# Komar.net
KiCad netlist of a schematic drawn in EAGLE
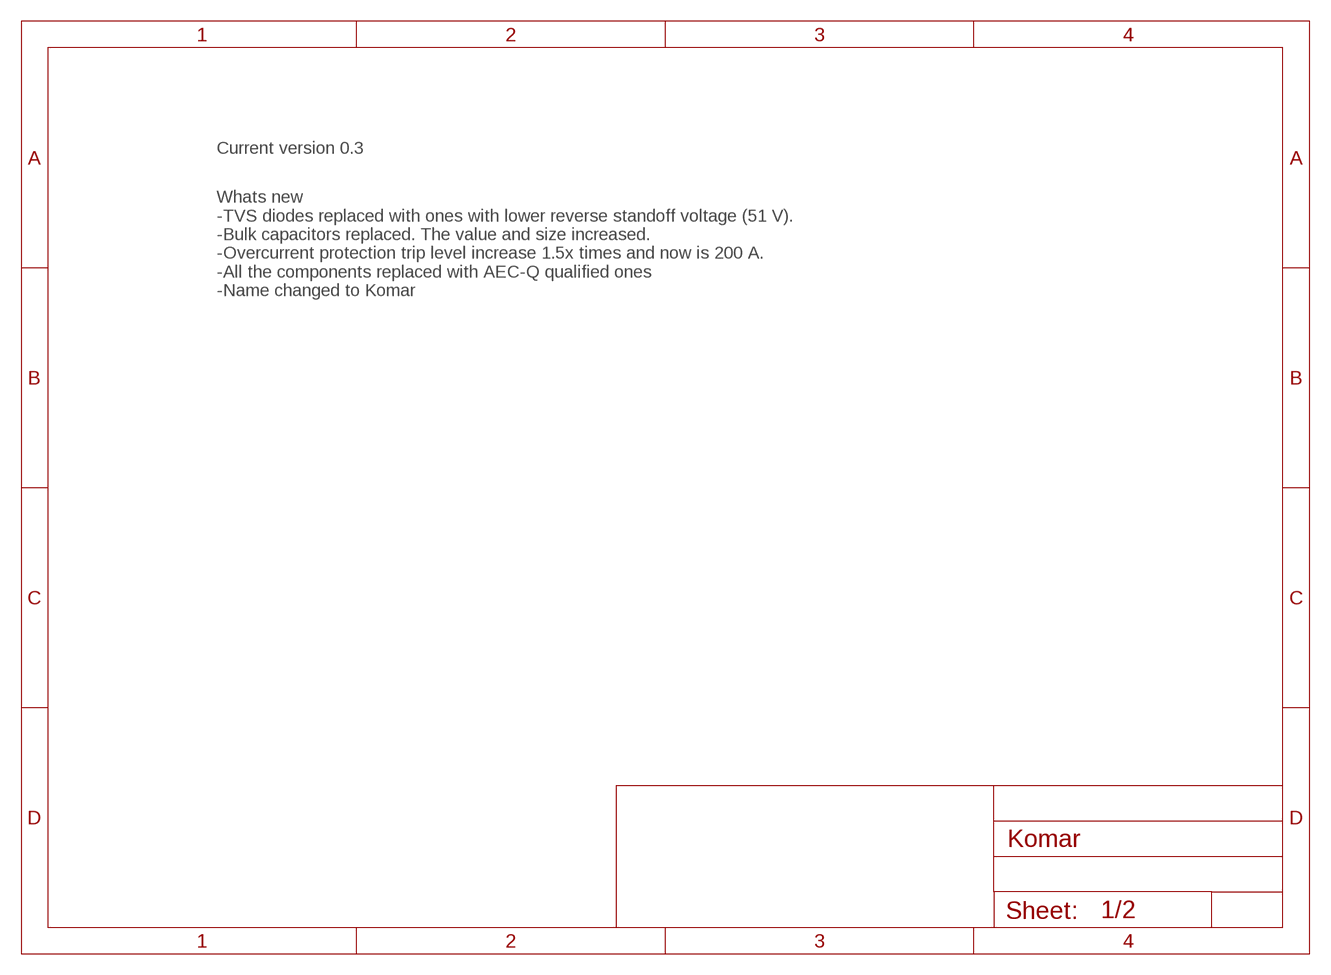
[diagram p0: schematic, sheet 1]
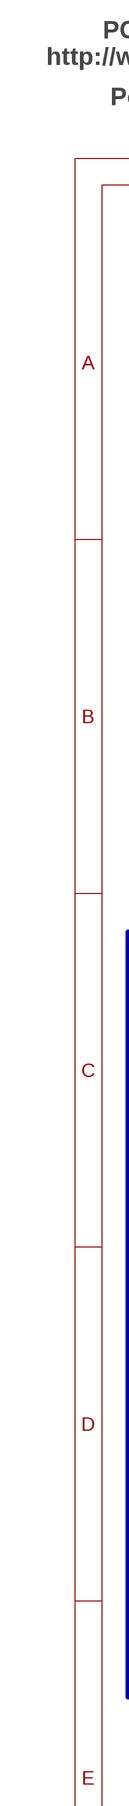
[diagram p1: schematic, sheet 2, part 1 of 2]
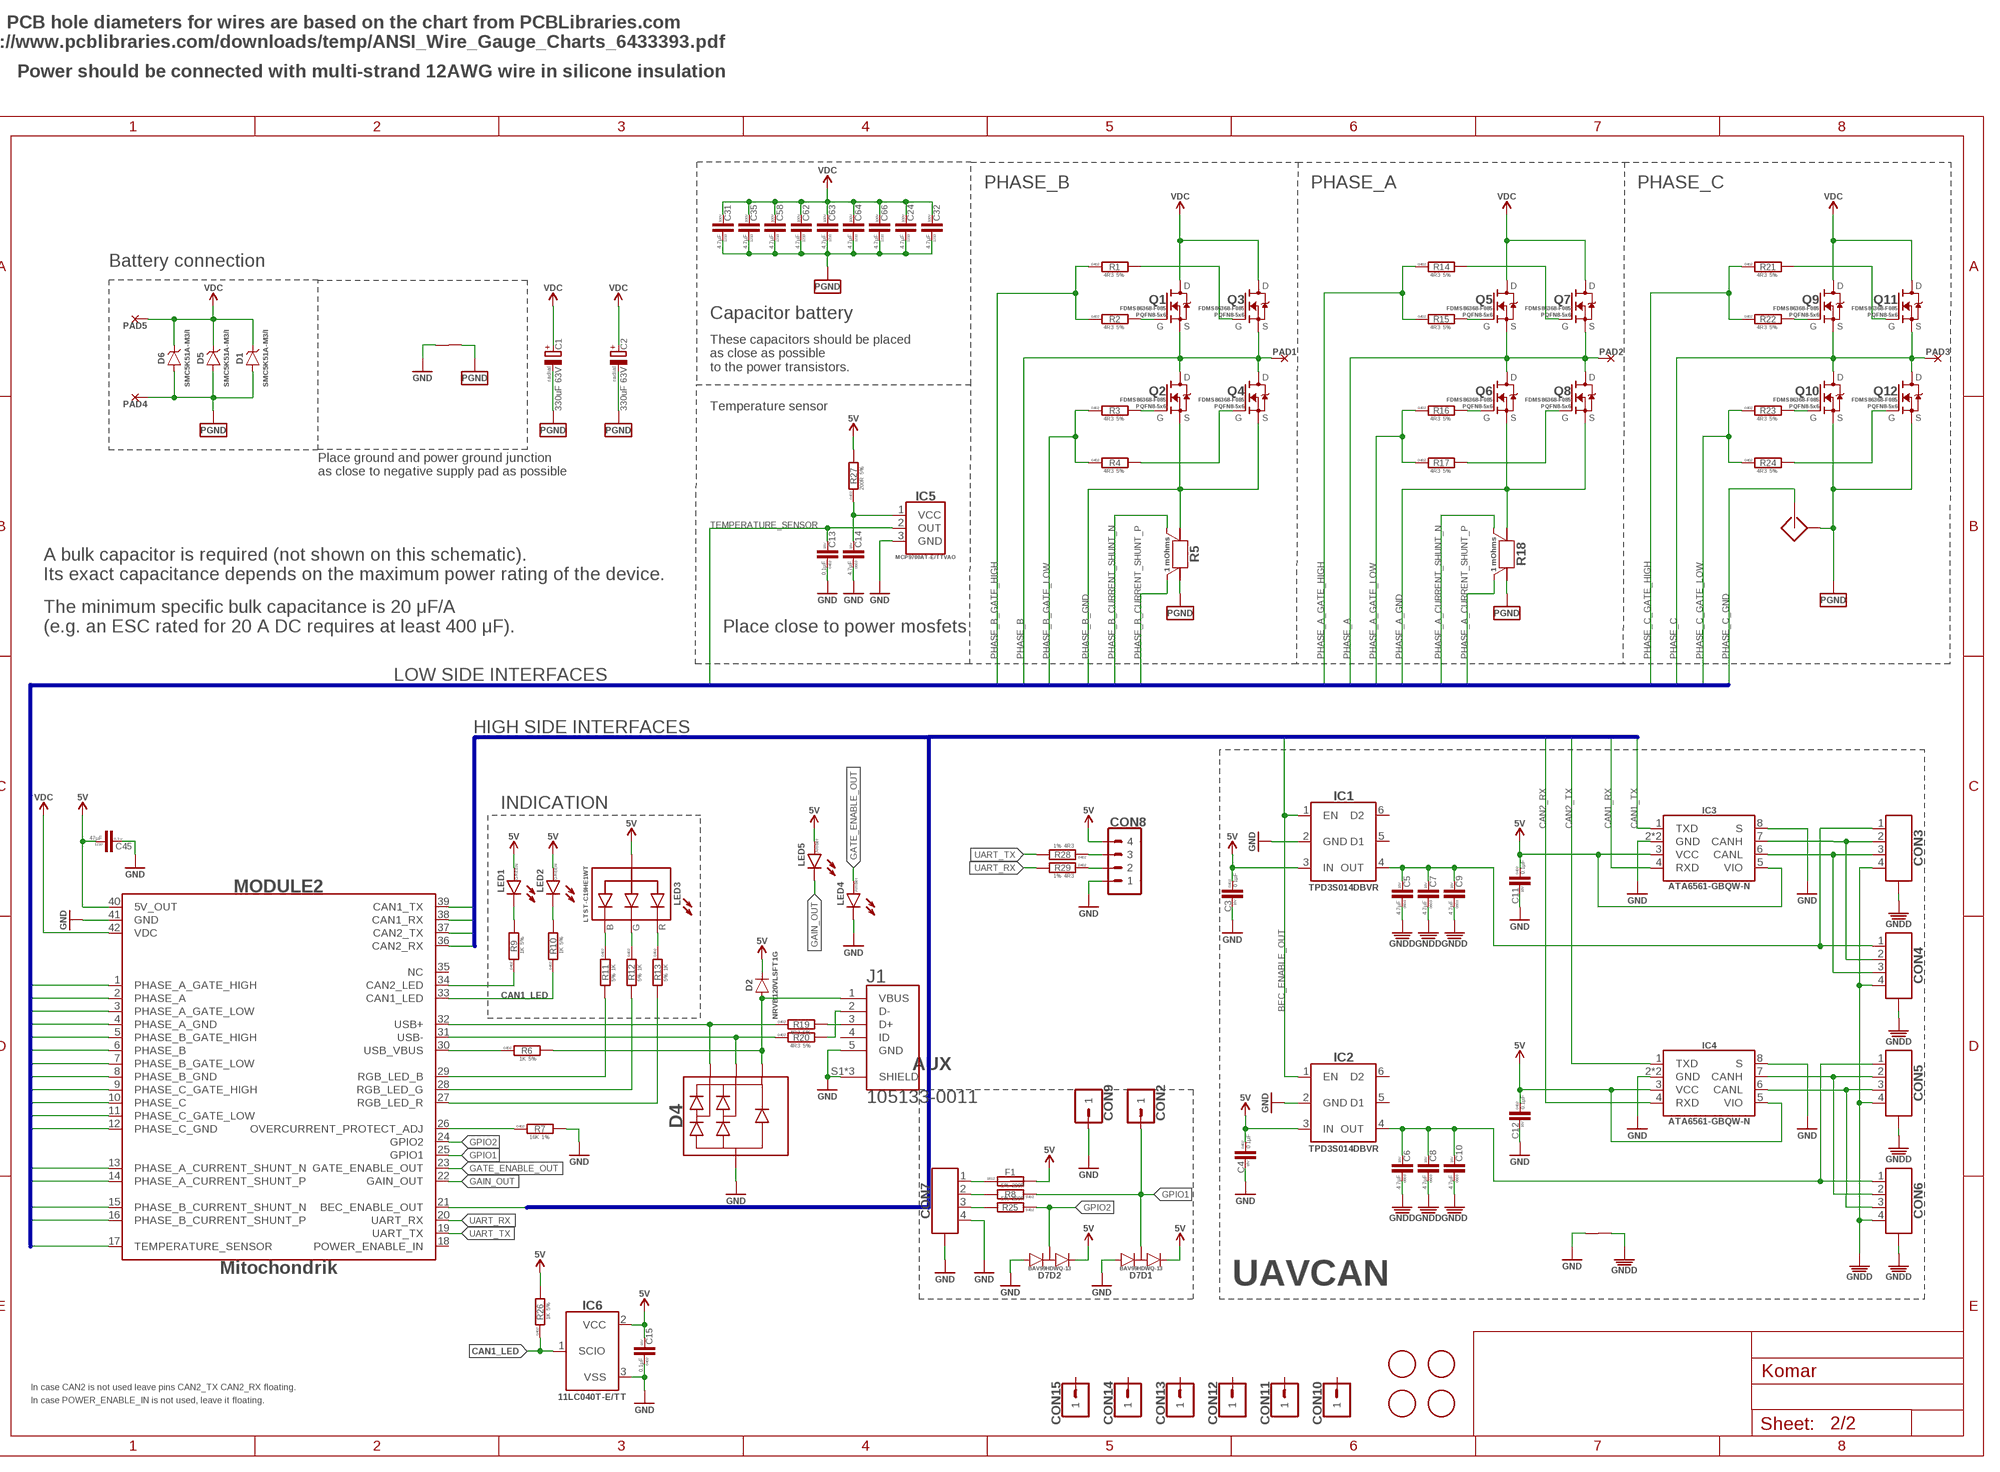
[diagram p2: schematic, sheet 2, part 2 of 2]

(export (version "E")
  (design (tool "Eeschema 10.0.6"))
  (components
    (comp (ref "C1")
      (value "330uF 63V")
      (footprint "eagle-import:SIDE_10X22")
      (fields
        (field (name "PACKAGE") "radial")
        (field (name "MANF") "EPCOS (TDK)")
        (field (name "DIGIKEY#") "565-2043-ND")
        (field (name "MANF_1") "United Chemi-Con")
        (field (name "MANF#") "ELXZ630ELL331MK20S")
      )
      (libsource (lib "eagle-import") (part "CPOL-SIDE"))
    )
    (comp (ref "C2")
      (value "330uF 63V")
      (footprint "eagle-import:SIDE_10X22")
      (fields
        (field (name "PACKAGE") "radial")
        (field (name "MANF") "EPCOS (TDK)")
        (field (name "DIGIKEY#") "565-2043-ND")
        (field (name "MANF_1") "United Chemi-Con")
        (field (name "MANF#") "ELXZ630ELL331MK20S")
      )
      (libsource (lib "eagle-import") (part "CPOL-SIDE"))
    )
    (comp (ref "C3")
      (value "0.1µF")
      (footprint "eagle-import:C0402")
      (fields
        (field (name "PACKAGE") "0402")
        (field (name "AEC-Q") "AEC-Q200")
        (field (name "DIGIKEY#") "490-7998-1-ND")
        (field (name "MANF") "Murata Electronics")
        (field (name "MANF#") "GCM155R71C104KA55J")
        (field (name "VOLTAGE") "16V")
      )
      (libsource (lib "eagle-import") (part "C-0402"))
    )
    (comp (ref "C4")
      (value "0.1µF")
      (footprint "eagle-import:C0402")
      (fields
        (field (name "PACKAGE") "0402")
        (field (name "AEC-Q") "AEC-Q200")
        (field (name "DIGIKEY#") "490-7998-1-ND")
        (field (name "MANF") "Murata Electronics")
        (field (name "MANF#") "GCM155R71C104KA55J")
        (field (name "VOLTAGE") "16V")
      )
      (libsource (lib "eagle-import") (part "C-0402"))
    )
    (comp (ref "C5")
      (value "4.7µF")
      (footprint "eagle-import:C0603")
      (fields
        (field (name "PACKAGE") "0603")
        (field (name "AEC-Q") "AEC-Q200")
        (field (name "DIGIKEY#") "490-12289-1-ND")
        (field (name "MANF") "Murata Electronics")
        (field (name "MANF#") "GRT188C81C475KE13D")
        (field (name "VOLTAGE") "16V")
      )
      (libsource (lib "eagle-import") (part "C-0603"))
    )
    (comp (ref "C6")
      (value "4.7µF")
      (footprint "eagle-import:C0603")
      (fields
        (field (name "PACKAGE") "0603")
        (field (name "AEC-Q") "AEC-Q200")
        (field (name "DIGIKEY#") "490-12289-1-ND")
        (field (name "MANF") "Murata Electronics")
        (field (name "MANF#") "GRT188C81C475KE13D")
        (field (name "VOLTAGE") "16V")
      )
      (libsource (lib "eagle-import") (part "C-0603"))
    )
    (comp (ref "C7")
      (value "4.7µF")
      (footprint "eagle-import:C0603")
      (fields
        (field (name "PACKAGE") "0603")
        (field (name "AEC-Q") "AEC-Q200")
        (field (name "DIGIKEY#") "490-12289-1-ND")
        (field (name "MANF") "Murata Electronics")
        (field (name "MANF#") "GRT188C81C475KE13D")
        (field (name "VOLTAGE") "16V")
      )
      (libsource (lib "eagle-import") (part "C-0603"))
    )
    (comp (ref "C8")
      (value "4.7µF")
      (footprint "eagle-import:C0603")
      (fields
        (field (name "PACKAGE") "0603")
        (field (name "AEC-Q") "AEC-Q200")
        (field (name "DIGIKEY#") "490-12289-1-ND")
        (field (name "MANF") "Murata Electronics")
        (field (name "MANF#") "GRT188C81C475KE13D")
        (field (name "VOLTAGE") "16V")
      )
      (libsource (lib "eagle-import") (part "C-0603"))
    )
    (comp (ref "C9")
      (value "4.7µF")
      (footprint "eagle-import:C0603")
      (fields
        (field (name "PACKAGE") "0603")
        (field (name "AEC-Q") "AEC-Q200")
        (field (name "DIGIKEY#") "490-12289-1-ND")
        (field (name "MANF") "Murata Electronics")
        (field (name "MANF#") "GRT188C81C475KE13D")
        (field (name "VOLTAGE") "16V")
      )
      (libsource (lib "eagle-import") (part "C-0603"))
    )
    (comp (ref "C10")
      (value "4.7µF")
      (footprint "eagle-import:C0603")
      (fields
        (field (name "PACKAGE") "0603")
        (field (name "AEC-Q") "AEC-Q200")
        (field (name "DIGIKEY#") "490-12289-1-ND")
        (field (name "MANF") "Murata Electronics")
        (field (name "MANF#") "GRT188C81C475KE13D")
        (field (name "VOLTAGE") "16V")
      )
      (libsource (lib "eagle-import") (part "C-0603"))
    )
    (comp (ref "C11")
      (value "0.1µF")
      (footprint "eagle-import:C0402")
      (fields
        (field (name "PACKAGE") "0402")
        (field (name "AEC-Q") "AEC-Q200")
        (field (name "DIGIKEY#") "490-7998-1-ND")
        (field (name "MANF") "Murata Electronics")
        (field (name "MANF#") "GCM155R71C104KA55J")
        (field (name "VOLTAGE") "16V")
      )
      (libsource (lib "eagle-import") (part "C-0402"))
    )
    (comp (ref "C12")
      (value "0.1µF")
      (footprint "eagle-import:C0402")
      (fields
        (field (name "PACKAGE") "0402")
        (field (name "AEC-Q") "AEC-Q200")
        (field (name "DIGIKEY#") "490-7998-1-ND")
        (field (name "MANF") "Murata Electronics")
        (field (name "MANF#") "GCM155R71C104KA55J")
        (field (name "VOLTAGE") "16V")
      )
      (libsource (lib "eagle-import") (part "C-0402"))
    )
    (comp (ref "C13")
      (value "0.1µF")
      (footprint "eagle-import:C0402")
      (fields
        (field (name "PACKAGE") "0402")
        (field (name "AEC-Q") "AEC-Q200")
        (field (name "DIGIKEY#") "490-7998-1-ND")
        (field (name "MANF") "Murata Electronics")
        (field (name "MANF#") "GCM155R71C104KA55J")
        (field (name "VOLTAGE") "16V")
      )
      (libsource (lib "eagle-import") (part "C-0402"))
    )
    (comp (ref "C14")
      (value "4.7µF")
      (footprint "eagle-import:C0603")
      (fields
        (field (name "PACKAGE") "0603")
        (field (name "AEC-Q") "AEC-Q200")
        (field (name "DIGIKEY#") "490-12289-1-ND")
        (field (name "MANF") "Murata Electronics")
        (field (name "MANF#") "GRT188C81C475KE13D")
        (field (name "VOLTAGE") "16V")
      )
      (libsource (lib "eagle-import") (part "C-0603"))
    )
    (comp (ref "C15")
      (value "0.1µF")
      (footprint "eagle-import:C0402")
      (fields
        (field (name "PACKAGE") "0402")
        (field (name "AEC-Q") "AEC-Q200")
        (field (name "DIGIKEY#") "490-7998-1-ND")
        (field (name "MANF") "Murata Electronics")
        (field (name "MANF#") "GCM155R71C104KA55J")
        (field (name "VOLTAGE") "16V")
      )
      (libsource (lib "eagle-import") (part "C-0402"))
    )
    (comp (ref "C24")
      (value "4.7µF")
      (footprint "eagle-import:C1210")
      (fields
        (field (name "PACKAGE") "1210")
        (field (name "DIGIKEY#") "490-14484-1-ND")
        (field (name "MANF") "Murata Electronics")
        (field (name "MANF#") "GCM32DC72A475KE02L")
        (field (name "OPERATING_TEMP") "-55°C ~ 125°C")
        (field (name "VOLTAGE") "100V")
      )
      (libsource (lib "eagle-import") (part "C-1210"))
    )
    (comp (ref "C31")
      (value "4.7µF")
      (footprint "eagle-import:C1210")
      (fields
        (field (name "PACKAGE") "1210")
        (field (name "DIGIKEY#") "490-14484-1-ND")
        (field (name "MANF") "Murata Electronics")
        (field (name "MANF#") "GCM32DC72A475KE02L")
        (field (name "OPERATING_TEMP") "-55°C ~ 125°C")
        (field (name "VOLTAGE") "100V")
      )
      (libsource (lib "eagle-import") (part "C-1210"))
    )
    (comp (ref "C32")
      (value "4.7µF")
      (footprint "eagle-import:C1210")
      (fields
        (field (name "PACKAGE") "1210")
        (field (name "DIGIKEY#") "490-14484-1-ND")
        (field (name "MANF") "Murata Electronics")
        (field (name "MANF#") "GCM32DC72A475KE02L")
        (field (name "OPERATING_TEMP") "-55°C ~ 125°C")
        (field (name "VOLTAGE") "100V")
      )
      (libsource (lib "eagle-import") (part "C-1210"))
    )
    (comp (ref "C35")
      (value "4.7µF")
      (footprint "eagle-import:C1210")
      (fields
        (field (name "PACKAGE") "1210")
        (field (name "DIGIKEY#") "490-14484-1-ND")
        (field (name "MANF") "Murata Electronics")
        (field (name "MANF#") "GCM32DC72A475KE02L")
        (field (name "OPERATING_TEMP") "-55°C ~ 125°C")
        (field (name "VOLTAGE") "100V")
      )
      (libsource (lib "eagle-import") (part "C-1210"))
    )
    (comp (ref "C45")
      (value "47µF")
      (footprint "eagle-import:C1210")
      (fields
        (field (name "PACKAGE") "1210")
        (field (name "DIGIKEY#") "490-4844-1-ND")
        (field (name "MANF") "Murata Electronics")
        (field (name "MANF#") "GCM32ER70J476KE19L")
        (field (name "OPERATING_TEMP") "-55°C ~ 125°C")
        (field (name "VOLTAGE") "6.3 V")
      )
      (libsource (lib "eagle-import") (part "C-1210"))
    )
    (comp (ref "C58")
      (value "4.7µF")
      (footprint "eagle-import:C1210")
      (fields
        (field (name "PACKAGE") "1210")
        (field (name "DIGIKEY#") "490-14484-1-ND")
        (field (name "MANF") "Murata Electronics")
        (field (name "MANF#") "GCM32DC72A475KE02L")
        (field (name "OPERATING_TEMP") "-55°C ~ 125°C")
        (field (name "VOLTAGE") "100V")
      )
      (libsource (lib "eagle-import") (part "C-1210"))
    )
    (comp (ref "C62")
      (value "4.7µF")
      (footprint "eagle-import:C1210")
      (fields
        (field (name "PACKAGE") "1210")
        (field (name "DIGIKEY#") "490-14484-1-ND")
        (field (name "MANF") "Murata Electronics")
        (field (name "MANF#") "GCM32DC72A475KE02L")
        (field (name "OPERATING_TEMP") "-55°C ~ 125°C")
        (field (name "VOLTAGE") "100V")
      )
      (libsource (lib "eagle-import") (part "C-1210"))
    )
    (comp (ref "C63")
      (value "4.7µF")
      (footprint "eagle-import:C1210")
      (fields
        (field (name "PACKAGE") "1210")
        (field (name "DIGIKEY#") "490-14484-1-ND")
        (field (name "MANF") "Murata Electronics")
        (field (name "MANF#") "GCM32DC72A475KE02L")
        (field (name "OPERATING_TEMP") "-55°C ~ 125°C")
        (field (name "VOLTAGE") "100V")
      )
      (libsource (lib "eagle-import") (part "C-1210"))
    )
    (comp (ref "C64")
      (value "4.7µF")
      (footprint "eagle-import:C1210")
      (fields
        (field (name "PACKAGE") "1210")
        (field (name "DIGIKEY#") "490-14484-1-ND")
        (field (name "MANF") "Murata Electronics")
        (field (name "MANF#") "GCM32DC72A475KE02L")
        (field (name "OPERATING_TEMP") "-55°C ~ 125°C")
        (field (name "VOLTAGE") "100V")
      )
      (libsource (lib "eagle-import") (part "C-1210"))
    )
    (comp (ref "C66")
      (value "4.7µF")
      (footprint "eagle-import:C1210")
      (fields
        (field (name "PACKAGE") "1210")
        (field (name "DIGIKEY#") "490-14484-1-ND")
        (field (name "MANF") "Murata Electronics")
        (field (name "MANF#") "GCM32DC72A475KE02L")
        (field (name "OPERATING_TEMP") "-55°C ~ 125°C")
        (field (name "VOLTAGE") "100V")
      )
      (libsource (lib "eagle-import") (part "C-1210"))
    )
    (comp (ref "CON2")
      (value "PINHEAD_1X01-2")
      (footprint "eagle-import:1X01-PTH-2")
      (libsource (lib "eagle-import") (part "PINHEAD_1X01-2"))
    )
    (comp (ref "CON3")
      (value "CON-4P-TABS-STRAIGHT")
      (footprint "eagle-import:JST_GH-4P-STRAIGHT")
      (fields (field (name "MANF") "JST Sales America Inc"))
      (libsource (lib "eagle-import") (part "CON-4P-TABS-STRAIGHT"))
    )
    (comp (ref "CON4")
      (value "CON-4P-TABS-STRAIGHT")
      (footprint "eagle-import:JST_GH-4P-STRAIGHT")
      (fields (field (name "MANF") "JST Sales America Inc"))
      (libsource (lib "eagle-import") (part "CON-4P-TABS-STRAIGHT"))
    )
    (comp (ref "CON5")
      (value "CON-4P-TABS-STRAIGHT")
      (footprint "eagle-import:JST_GH-4P-STRAIGHT")
      (fields (field (name "MANF") "JST Sales America Inc"))
      (libsource (lib "eagle-import") (part "CON-4P-TABS-STRAIGHT"))
    )
    (comp (ref "CON6")
      (value "CON-4P-TABS-STRAIGHT")
      (footprint "eagle-import:JST_GH-4P-STRAIGHT")
      (fields (field (name "MANF") "JST Sales America Inc"))
      (libsource (lib "eagle-import") (part "CON-4P-TABS-STRAIGHT"))
    )
    (comp (ref "CON7")
      (value "CON-4P-TABS-STRAIGHT")
      (footprint "eagle-import:JST_GH-4P-STRAIGHT")
      (fields (field (name "MANF") "JST Sales America Inc"))
      (libsource (lib "eagle-import") (part "CON-4P-TABS-STRAIGHT"))
    )
    (comp (ref "CON8")
      (value "PINHEAD_1X04-2")
      (footprint "eagle-import:1X04-PTH-2")
      (libsource (lib "eagle-import") (part "PINHEAD_1X04-2"))
    )
    (comp (ref "CON9")
      (value "PINHEAD_1X01-2")
      (footprint "eagle-import:1X01-PTH-2")
      (libsource (lib "eagle-import") (part "PINHEAD_1X01-2"))
    )
    (comp (ref "CON10")
      (value "PINHEAD_1X01-2")
      (footprint "eagle-import:1X01-PTH-2")
      (libsource (lib "eagle-import") (part "PINHEAD_1X01-2"))
    )
    (comp (ref "CON11")
      (value "PINHEAD_1X01-2")
      (footprint "eagle-import:1X01-PTH-2")
      (libsource (lib "eagle-import") (part "PINHEAD_1X01-2"))
    )
    (comp (ref "CON12")
      (value "PINHEAD_1X01-2")
      (footprint "eagle-import:1X01-PTH-2")
      (libsource (lib "eagle-import") (part "PINHEAD_1X01-2"))
    )
    (comp (ref "CON13")
      (value "PINHEAD_1X01-2")
      (footprint "eagle-import:1X01-PTH-2")
      (libsource (lib "eagle-import") (part "PINHEAD_1X01-2"))
    )
    (comp (ref "CON14")
      (value "PINHEAD_1X01-2")
      (footprint "eagle-import:1X01-PTH-2")
      (libsource (lib "eagle-import") (part "PINHEAD_1X01-2"))
    )
    (comp (ref "CON15")
      (value "PINHEAD_1X01-2")
      (footprint "eagle-import:1X01-PTH-2")
      (libsource (lib "eagle-import") (part "PINHEAD_1X01-2"))
    )
    (comp (ref "D1")
      (value "SMC5K51A-M3/I")
      (footprint "eagle-import:DO-214AB(SMC)")
      (fields
        (field (name "MANF#") "SMC5K51A-M3/I")
        (field (name "MANF") "Vishay Semiconductor Diodes Division")
      )
      (libsource (lib "eagle-import") (part "SMC5K51A-M3/I"))
    )
    (comp (ref "D2")
      (value "NRVB120VLSFT1G")
      (footprint "eagle-import:SOD123F")
      (fields (field (name "MANF#") "NRVB120VLSFT1G") (field (name "MANF") "ON Semiconductor"))
      (libsource (lib "eagle-import") (part "NRVB120VLSFT1G"))
    )
    (comp (ref "D4")
      (value "DRTR5V0U2SR-7")
      (footprint "eagle-import:SOT143B")
      (fields (field (name "MANF") "Diodes Incorporated"))
      (libsource (lib "eagle-import") (part "DRTR5V0U2SR-7"))
    )
    (comp (ref "D5")
      (value "SMC5K51A-M3/I")
      (footprint "eagle-import:DO-214AB(SMC)")
      (fields
        (field (name "MANF#") "SMC5K51A-M3/I")
        (field (name "MANF") "Vishay Semiconductor Diodes Division")
      )
      (libsource (lib "eagle-import") (part "SMC5K51A-M3/I"))
    )
    (comp (ref "D6")
      (value "SMC5K51A-M3/I")
      (footprint "eagle-import:DO-214AB(SMC)")
      (fields
        (field (name "MANF#") "SMC5K51A-M3/I")
        (field (name "MANF") "Vishay Semiconductor Diodes Division")
      )
      (libsource (lib "eagle-import") (part "SMC5K51A-M3/I"))
    )
    (comp (ref "D7")
      (value "BAV99HDWQ-13")
      (footprint "eagle-import:SOT363")
      (fields (field (name "MANF#") "BAV99HDWQ-13") (field (name "MANF") "Diodes Incorporated"))
      (libsource (lib "eagle-import") (part "BAV99HDWQ-13"))
    )
    (comp (ref "F1")
      (value "FUSE-1812")
      (footprint "eagle-import:F1812")
      (fields (field (name "PACKAGE") "1812") (field (name "MANF") "Bourns Inc."))
      (libsource (lib "eagle-import") (part "FUSE-1812"))
    )
    (comp (ref "IC1")
      (value "TPD3S014DBVR-SOT23-6")
      (footprint "eagle-import:SOT26")
      (fields (field (name "MANF#") "TPD3S014DBVR") (field (name "MANF") "Texas Instruments"))
      (libsource (lib "eagle-import") (part "TPD3S014DBVR-SOT23-6"))
    )
    (comp (ref "IC2")
      (value "TPD3S014DBVR-SOT23-6")
      (footprint "eagle-import:SOT26")
      (fields (field (name "MANF#") "TPD3S014DBVR") (field (name "MANF") "Texas Instruments"))
      (libsource (lib "eagle-import") (part "TPD3S014DBVR-SOT23-6"))
    )
    (comp (ref "IC3")
      (value "ATA6561-GBQW-N-HVSON8")
      (footprint "eagle-import:SOT782-1")
      (fields (field (name "MANF#") "ATA6561-GBQW-N") (field (name "MANF") "Microchip Technology"))
      (libsource (lib "eagle-import") (part "ATA6561-GBQW-N-HVSON8"))
    )
    (comp (ref "IC4")
      (value "ATA6561-GBQW-N-HVSON8")
      (footprint "eagle-import:SOT782-1")
      (fields (field (name "MANF#") "ATA6561-GBQW-N") (field (name "MANF") "Microchip Technology"))
      (libsource (lib "eagle-import") (part "ATA6561-GBQW-N-HVSON8"))
    )
    (comp (ref "IC5")
      (value "MCP9700AT-E/TTVAO-SOT23")
      (footprint "eagle-import:SOT23B-3")
      (fields (field (name "MANF") "Microchip Technology") (field (name "MANF#") "MCP9700AT-E/TTVAO"))
      (libsource (lib "eagle-import") (part "MCP9700-SOT23AT-E/TTVAO"))
    )
    (comp (ref "IC6")
      (value "11LC040T-E/TT")
      (footprint "eagle-import:SOT23B-3")
      (fields (field (name "MANF#") "11LC040T-E/TT") (field (name "MANF") "Microchip Technology"))
      (libsource (lib "eagle-import") (part "11LC040T-E/TT"))
    )
    (comp (ref "J1")
      (value "105133-0011")
      (footprint "eagle-import:MOLEX_105133-0011")
      (fields
        (field (name "MANF") "Molex")
        (field (name "AEC-Q") "---")
        (field (name "DIGIKEY#") "WM10134TR-ND")
        (field (name "MANF_1") "Molex")
        (field (name "MANF#") "105133-0011")
        (field (name "OPERATING_TEMP") "-35°C ~ 85°C")
      )
      (libsource (lib "eagle-import") (part "105133-0011"))
    )
    (comp (ref "LED1")
      (value "GREEN")
      (footprint "eagle-import:LED0402")
      (fields
        (field (name "COLOR") "GREEN")
        (field (name "DIGIKEY#") "1830-IN-S42BT5GCT-ND")
        (field (name "MANF") "Inolux")
        (field (name "MANF#") "IN-S42BT5G")
      )
      (libsource (lib "eagle-import") (part "LED-0402"))
    )
    (comp (ref "LED2")
      (value "GREEN")
      (footprint "eagle-import:LED0402")
      (fields
        (field (name "COLOR") "GREEN")
        (field (name "DIGIKEY#") "1830-IN-S42BT5GCT-ND")
        (field (name "MANF") "Inolux")
        (field (name "MANF#") "IN-S42BT5G")
      )
      (libsource (lib "eagle-import") (part "LED-0402"))
    )
    (comp (ref "LED3")
      (value "LTST-C19HE1WT")
      (footprint "eagle-import:0606")
      (fields (field (name "MANF#") "LTST-C19HE1WT") (field (name "MANF") "Lite-On Inc"))
      (libsource (lib "eagle-import") (part "LTST-C19HE1WT"))
    )
    (comp (ref "LED4")
      (value "ORANGE")
      (footprint "eagle-import:LED0402")
      (fields
        (field (name "COLOR") "Amber")
        (field (name "DIGIKEY#") "1830-IN-S42BT5ACT-ND")
        (field (name "MANF") "Inolux")
        (field (name "MANF#") "IN-S42BT5A")
      )
      (libsource (lib "eagle-import") (part "LED-0402"))
    )
    (comp (ref "LED5")
      (value "ORANGE")
      (footprint "eagle-import:LED0402")
      (fields
        (field (name "COLOR") "Amber")
        (field (name "DIGIKEY#") "1830-IN-S42BT5ACT-ND")
        (field (name "MANF") "Inolux")
        (field (name "MANF#") "IN-S42BT5A")
      )
      (libsource (lib "eagle-import") (part "LED-0402"))
    )
    (comp (ref "MODULE2")
      (value "MITOCHONDRIK_LV-TH")
      (footprint "eagle-import:MITOHONDRIK-TH")
      (fields (field (name "MANF#") "Mitochondrik") (field (name "MANF") "Zubax Robotics"))
      (libsource (lib "eagle-import") (part "MITOCHONDRIK_LV-TH"))
    )
    (comp (ref "PAD1")
      (value "PAD-HOLE_2.4_SQUARE")
      (footprint "eagle-import:HOLE_2.4")
      (libsource (lib "eagle-import") (part "PAD-HOLE_2.4_SQUARE"))
    )
    (comp (ref "PAD2")
      (value "PAD-HOLE_2.4_SQUARE")
      (footprint "eagle-import:HOLE_2.4")
      (libsource (lib "eagle-import") (part "PAD-HOLE_2.4_SQUARE"))
    )
    (comp (ref "PAD3")
      (value "PAD-HOLE_2.4_SQUARE")
      (footprint "eagle-import:HOLE_2.4")
      (libsource (lib "eagle-import") (part "PAD-HOLE_2.4_SQUARE"))
    )
    (comp (ref "PAD4")
      (value "PAD-HOLE_2.8_SQUARE")
      (footprint "eagle-import:HOLE_2.8")
      (libsource (lib "eagle-import") (part "PAD-HOLE_2.8_SQUARE"))
    )
    (comp (ref "PAD5")
      (value "PAD-HOLE_2.8_SQUARE")
      (footprint "eagle-import:HOLE_2.8")
      (libsource (lib "eagle-import") (part "PAD-HOLE_2.8_SQUARE"))
    )
    (comp (ref "Q1")
      (value "FDMS86368-F085")
      (footprint "eagle-import:PQFN8_5X6")
      (fields
        (field (name "MANF#") "FDMS86368-F085")
        (field (name "PACKAGE") "PQFN8-5x6")
        (field (name "MANF") "ON Semiconductor")
      )
      (libsource (lib "eagle-import") (part "FDMS86368-F085"))
    )
    (comp (ref "Q2")
      (value "FDMS86368-F085")
      (footprint "eagle-import:PQFN8_5X6")
      (fields
        (field (name "MANF#") "FDMS86368-F085")
        (field (name "PACKAGE") "PQFN8-5x6")
        (field (name "MANF") "ON Semiconductor")
      )
      (libsource (lib "eagle-import") (part "FDMS86368-F085"))
    )
    (comp (ref "Q3")
      (value "FDMS86368-F085")
      (footprint "eagle-import:PQFN8_5X6")
      (fields
        (field (name "MANF#") "FDMS86368-F085")
        (field (name "PACKAGE") "PQFN8-5x6")
        (field (name "MANF") "ON Semiconductor")
      )
      (libsource (lib "eagle-import") (part "FDMS86368-F085"))
    )
    (comp (ref "Q4")
      (value "FDMS86368-F085")
      (footprint "eagle-import:PQFN8_5X6")
      (fields
        (field (name "MANF#") "FDMS86368-F085")
        (field (name "PACKAGE") "PQFN8-5x6")
        (field (name "MANF") "ON Semiconductor")
      )
      (libsource (lib "eagle-import") (part "FDMS86368-F085"))
    )
    (comp (ref "Q5")
      (value "FDMS86368-F085")
      (footprint "eagle-import:PQFN8_5X6")
      (fields
        (field (name "MANF#") "FDMS86368-F085")
        (field (name "PACKAGE") "PQFN8-5x6")
        (field (name "MANF") "ON Semiconductor")
      )
      (libsource (lib "eagle-import") (part "FDMS86368-F085"))
    )
    (comp (ref "Q6")
      (value "FDMS86368-F085")
      (footprint "eagle-import:PQFN8_5X6")
      (fields
        (field (name "MANF#") "FDMS86368-F085")
        (field (name "PACKAGE") "PQFN8-5x6")
        (field (name "MANF") "ON Semiconductor")
      )
      (libsource (lib "eagle-import") (part "FDMS86368-F085"))
    )
    (comp (ref "Q7")
      (value "FDMS86368-F085")
      (footprint "eagle-import:PQFN8_5X6")
      (fields
        (field (name "MANF#") "FDMS86368-F085")
        (field (name "PACKAGE") "PQFN8-5x6")
        (field (name "MANF") "ON Semiconductor")
      )
      (libsource (lib "eagle-import") (part "FDMS86368-F085"))
    )
    (comp (ref "Q8")
      (value "FDMS86368-F085")
      (footprint "eagle-import:PQFN8_5X6")
      (fields
        (field (name "MANF#") "FDMS86368-F085")
        (field (name "PACKAGE") "PQFN8-5x6")
        (field (name "MANF") "ON Semiconductor")
      )
      (libsource (lib "eagle-import") (part "FDMS86368-F085"))
    )
    (comp (ref "Q9")
      (value "FDMS86368-F085")
      (footprint "eagle-import:PQFN8_5X6")
      (fields
        (field (name "MANF#") "FDMS86368-F085")
        (field (name "PACKAGE") "PQFN8-5x6")
        (field (name "MANF") "ON Semiconductor")
      )
      (libsource (lib "eagle-import") (part "FDMS86368-F085"))
    )
    (comp (ref "Q10")
      (value "FDMS86368-F085")
      (footprint "eagle-import:PQFN8_5X6")
      (fields
        (field (name "MANF#") "FDMS86368-F085")
        (field (name "PACKAGE") "PQFN8-5x6")
        (field (name "MANF") "ON Semiconductor")
      )
      (libsource (lib "eagle-import") (part "FDMS86368-F085"))
    )
    (comp (ref "Q11")
      (value "FDMS86368-F085")
      (footprint "eagle-import:PQFN8_5X6")
      (fields
        (field (name "MANF#") "FDMS86368-F085")
        (field (name "PACKAGE") "PQFN8-5x6")
        (field (name "MANF") "ON Semiconductor")
      )
      (libsource (lib "eagle-import") (part "FDMS86368-F085"))
    )
    (comp (ref "Q12")
      (value "FDMS86368-F085")
      (footprint "eagle-import:PQFN8_5X6")
      (fields
        (field (name "MANF#") "FDMS86368-F085")
        (field (name "PACKAGE") "PQFN8-5x6")
        (field (name "MANF") "ON Semiconductor")
      )
      (libsource (lib "eagle-import") (part "FDMS86368-F085"))
    )
    (comp (ref "R1")
      (value "4R3")
      (footprint "eagle-import:R0402")
      (fields
        (field (name "PACKAGE") "0402")
        (field (name "TOLERANCE") "5%")
        (field (name "AEC-Q") "AEC-Q200")
        (field (name "DIGIKEY#") "P4.3JCT-ND")
        (field (name "MANF") "Panasonic Electronic Components")
        (field (name "MANF#") "ERJ-2GEJ4R3X")
      )
      (libsource (lib "eagle-import") (part "R-0402-5%"))
    )
    (comp (ref "R2")
      (value "4R3")
      (footprint "eagle-import:R0402")
      (fields
        (field (name "PACKAGE") "0402")
        (field (name "TOLERANCE") "5%")
        (field (name "AEC-Q") "AEC-Q200")
        (field (name "DIGIKEY#") "P4.3JCT-ND")
        (field (name "MANF") "Panasonic Electronic Components")
        (field (name "MANF#") "ERJ-2GEJ4R3X")
      )
      (libsource (lib "eagle-import") (part "R-0402-5%"))
    )
    (comp (ref "R3")
      (value "4R3")
      (footprint "eagle-import:R0402")
      (fields
        (field (name "PACKAGE") "0402")
        (field (name "TOLERANCE") "5%")
        (field (name "AEC-Q") "AEC-Q200")
        (field (name "DIGIKEY#") "P4.3JCT-ND")
        (field (name "MANF") "Panasonic Electronic Components")
        (field (name "MANF#") "ERJ-2GEJ4R3X")
      )
      (libsource (lib "eagle-import") (part "R-0402-5%"))
    )
    (comp (ref "R4")
      (value "4R3")
      (footprint "eagle-import:R0402")
      (fields
        (field (name "PACKAGE") "0402")
        (field (name "TOLERANCE") "5%")
        (field (name "AEC-Q") "AEC-Q200")
        (field (name "DIGIKEY#") "P4.3JCT-ND")
        (field (name "MANF") "Panasonic Electronic Components")
        (field (name "MANF#") "ERJ-2GEJ4R3X")
      )
      (libsource (lib "eagle-import") (part "R-0402-5%"))
    )
    (comp (ref "R5")
      (value "1 mOhms")
      (footprint "eagle-import:R2512-KELVIN")
      (fields
        (field (name "MANF") "Stackpole Electronics Inc.")
        (field (name "POWER") "2W")
        (field (name "TOLERANCE") "±1%")
        (field (name "DIGIKEY#") "CRE2512-FZ-R001E-3CT-ND")
        (field (name "MANF_1") "Bourns Inc.")
        (field (name "MANF#") "CRE2512-FZ-R001E-3")
        (field (name "POWER_1") "3W")
      )
      (libsource (lib "eagle-import") (part "CURRENT_SHUNT_KELVIN-2512-KELVIN-0.001R"))
    )
    (comp (ref "R6")
      (value "1K")
      (footprint "eagle-import:R0402")
      (fields
        (field (name "PACKAGE") "0402")
        (field (name "TOLERANCE") "5%")
        (field (name "AEC-Q") "AEC-Q200")
        (field (name "DIGIKEY#") "P1.00KLCT-ND")
        (field (name "MANF") "Panasonic Electronic Components")
        (field (name "MANF#") "ERJ-2RKF1001X")
      )
      (libsource (lib "eagle-import") (part "R-0402-5%"))
    )
    (comp (ref "R7")
      (value "16K")
      (footprint "eagle-import:R0402")
      (fields
        (field (name "PACKAGE") "0402")
        (field (name "TOLERANCE") "1%")
        (field (name "AEC-Q") "AEC-Q200")
        (field (name "DIGIKEY#") "P124444CT-ND")
        (field (name "MANF") "Panasonic Electronic Components")
        (field (name "MANF#") "ERJ-PA2F1602X")
      )
      (libsource (lib "eagle-import") (part "R-0402-1%"))
    )
    (comp (ref "R8")
      (value "200R")
      (footprint "eagle-import:R0402")
      (fields
        (field (name "PACKAGE") "0402")
        (field (name "TOLERANCE") "5%")
        (field (name "AEC-Q") "AEC-Q200")
        (field (name "DIGIKEY#") "P200JCT-ND")
        (field (name "MANF") "Panasonic Electronic Components")
        (field (name "MANF#") "ERJ-2GEJ201X")
      )
      (libsource (lib "eagle-import") (part "R-0402-5%"))
    )
    (comp (ref "R9")
      (value "1K")
      (footprint "eagle-import:R0402")
      (fields
        (field (name "PACKAGE") "0402")
        (field (name "TOLERANCE") "5%")
        (field (name "AEC-Q") "AEC-Q200")
        (field (name "DIGIKEY#") "P1.00KLCT-ND")
        (field (name "MANF") "Panasonic Electronic Components")
        (field (name "MANF#") "ERJ-2RKF1001X")
      )
      (libsource (lib "eagle-import") (part "R-0402-5%"))
    )
    (comp (ref "R10")
      (value "1K")
      (footprint "eagle-import:R0402")
      (fields
        (field (name "PACKAGE") "0402")
        (field (name "TOLERANCE") "5%")
        (field (name "AEC-Q") "AEC-Q200")
        (field (name "DIGIKEY#") "P1.00KLCT-ND")
        (field (name "MANF") "Panasonic Electronic Components")
        (field (name "MANF#") "ERJ-2RKF1001X")
      )
      (libsource (lib "eagle-import") (part "R-0402-5%"))
    )
    (comp (ref "R11")
      (value "1K")
      (footprint "eagle-import:R0402")
      (fields
        (field (name "PACKAGE") "0402")
        (field (name "TOLERANCE") "5%")
        (field (name "AEC-Q") "AEC-Q200")
        (field (name "DIGIKEY#") "P1.00KLCT-ND")
        (field (name "MANF") "Panasonic Electronic Components")
        (field (name "MANF#") "ERJ-2RKF1001X")
      )
      (libsource (lib "eagle-import") (part "R-0402-5%"))
    )
    (comp (ref "R12")
      (value "1K")
      (footprint "eagle-import:R0402")
      (fields
        (field (name "PACKAGE") "0402")
        (field (name "TOLERANCE") "5%")
        (field (name "AEC-Q") "AEC-Q200")
        (field (name "DIGIKEY#") "P1.00KLCT-ND")
        (field (name "MANF") "Panasonic Electronic Components")
        (field (name "MANF#") "ERJ-2RKF1001X")
      )
      (libsource (lib "eagle-import") (part "R-0402-5%"))
    )
    (comp (ref "R13")
      (value "1K")
      (footprint "eagle-import:R0402")
      (fields
        (field (name "PACKAGE") "0402")
        (field (name "TOLERANCE") "5%")
        (field (name "AEC-Q") "AEC-Q200")
        (field (name "DIGIKEY#") "P1.00KLCT-ND")
        (field (name "MANF") "Panasonic Electronic Components")
        (field (name "MANF#") "ERJ-2RKF1001X")
      )
      (libsource (lib "eagle-import") (part "R-0402-5%"))
    )
    (comp (ref "R14")
      (value "4R3")
      (footprint "eagle-import:R0402")
      (fields
        (field (name "PACKAGE") "0402")
        (field (name "TOLERANCE") "5%")
        (field (name "AEC-Q") "AEC-Q200")
        (field (name "DIGIKEY#") "P4.3JCT-ND")
        (field (name "MANF") "Panasonic Electronic Components")
        (field (name "MANF#") "ERJ-2GEJ4R3X")
      )
      (libsource (lib "eagle-import") (part "R-0402-5%"))
    )
    (comp (ref "R15")
      (value "4R3")
      (footprint "eagle-import:R0402")
      (fields
        (field (name "PACKAGE") "0402")
        (field (name "TOLERANCE") "5%")
        (field (name "AEC-Q") "AEC-Q200")
        (field (name "DIGIKEY#") "P4.3JCT-ND")
        (field (name "MANF") "Panasonic Electronic Components")
        (field (name "MANF#") "ERJ-2GEJ4R3X")
      )
      (libsource (lib "eagle-import") (part "R-0402-5%"))
    )
    (comp (ref "R16")
      (value "4R3")
      (footprint "eagle-import:R0402")
      (fields
        (field (name "PACKAGE") "0402")
        (field (name "TOLERANCE") "5%")
        (field (name "AEC-Q") "AEC-Q200")
        (field (name "DIGIKEY#") "P4.3JCT-ND")
        (field (name "MANF") "Panasonic Electronic Components")
        (field (name "MANF#") "ERJ-2GEJ4R3X")
      )
      (libsource (lib "eagle-import") (part "R-0402-5%"))
    )
    (comp (ref "R17")
      (value "4R3")
      (footprint "eagle-import:R0402")
      (fields
        (field (name "PACKAGE") "0402")
        (field (name "TOLERANCE") "5%")
        (field (name "AEC-Q") "AEC-Q200")
        (field (name "DIGIKEY#") "P4.3JCT-ND")
        (field (name "MANF") "Panasonic Electronic Components")
        (field (name "MANF#") "ERJ-2GEJ4R3X")
      )
      (libsource (lib "eagle-import") (part "R-0402-5%"))
    )
    (comp (ref "R18")
      (value "1 mOhms")
      (footprint "eagle-import:R2512-KELVIN")
      (fields
        (field (name "MANF") "Stackpole Electronics Inc.")
        (field (name "POWER") "2W")
        (field (name "TOLERANCE") "±1%")
        (field (name "DIGIKEY#") "CRE2512-FZ-R001E-3CT-ND")
        (field (name "MANF_1") "Bourns Inc.")
        (field (name "MANF#") "CRE2512-FZ-R001E-3")
        (field (name "POWER_1") "3W")
      )
      (libsource (lib "eagle-import") (part "CURRENT_SHUNT_KELVIN-2512-KELVIN-0.001R"))
    )
    (comp (ref "R19")
      (value "4R3")
      (footprint "eagle-import:R0402")
      (fields
        (field (name "PACKAGE") "0402")
        (field (name "TOLERANCE") "5%")
        (field (name "AEC-Q") "AEC-Q200")
        (field (name "DIGIKEY#") "P4.3JCT-ND")
        (field (name "MANF") "Panasonic Electronic Components")
        (field (name "MANF#") "ERJ-2GEJ4R3X")
      )
      (libsource (lib "eagle-import") (part "R-0402-5%"))
    )
    (comp (ref "R20")
      (value "4R3")
      (footprint "eagle-import:R0402")
      (fields
        (field (name "PACKAGE") "0402")
        (field (name "TOLERANCE") "5%")
        (field (name "AEC-Q") "AEC-Q200")
        (field (name "DIGIKEY#") "P4.3JCT-ND")
        (field (name "MANF") "Panasonic Electronic Components")
        (field (name "MANF#") "ERJ-2GEJ4R3X")
      )
      (libsource (lib "eagle-import") (part "R-0402-5%"))
    )
    (comp (ref "R21")
      (value "4R3")
      (footprint "eagle-import:R0402")
      (fields
        (field (name "PACKAGE") "0402")
        (field (name "TOLERANCE") "5%")
        (field (name "AEC-Q") "AEC-Q200")
        (field (name "DIGIKEY#") "P4.3JCT-ND")
        (field (name "MANF") "Panasonic Electronic Components")
        (field (name "MANF#") "ERJ-2GEJ4R3X")
      )
      (libsource (lib "eagle-import") (part "R-0402-5%"))
    )
    (comp (ref "R22")
      (value "4R3")
      (footprint "eagle-import:R0402")
      (fields
        (field (name "PACKAGE") "0402")
        (field (name "TOLERANCE") "5%")
        (field (name "AEC-Q") "AEC-Q200")
        (field (name "DIGIKEY#") "P4.3JCT-ND")
        (field (name "MANF") "Panasonic Electronic Components")
        (field (name "MANF#") "ERJ-2GEJ4R3X")
      )
      (libsource (lib "eagle-import") (part "R-0402-5%"))
    )
    (comp (ref "R23")
      (value "4R3")
      (footprint "eagle-import:R0402")
      (fields
        (field (name "PACKAGE") "0402")
        (field (name "TOLERANCE") "5%")
        (field (name "AEC-Q") "AEC-Q200")
        (field (name "DIGIKEY#") "P4.3JCT-ND")
        (field (name "MANF") "Panasonic Electronic Components")
        (field (name "MANF#") "ERJ-2GEJ4R3X")
      )
      (libsource (lib "eagle-import") (part "R-0402-5%"))
    )
    (comp (ref "R24")
      (value "4R3")
      (footprint "eagle-import:R0402")
      (fields
        (field (name "PACKAGE") "0402")
        (field (name "TOLERANCE") "5%")
        (field (name "AEC-Q") "AEC-Q200")
        (field (name "DIGIKEY#") "P4.3JCT-ND")
        (field (name "MANF") "Panasonic Electronic Components")
        (field (name "MANF#") "ERJ-2GEJ4R3X")
      )
      (libsource (lib "eagle-import") (part "R-0402-5%"))
    )
    (comp (ref "R25")
      (value "200R")
      (footprint "eagle-import:R0402")
      (fields
        (field (name "PACKAGE") "0402")
        (field (name "TOLERANCE") "5%")
        (field (name "AEC-Q") "AEC-Q200")
        (field (name "DIGIKEY#") "P200JCT-ND")
        (field (name "MANF") "Panasonic Electronic Components")
        (field (name "MANF#") "ERJ-2GEJ201X")
      )
      (libsource (lib "eagle-import") (part "R-0402-5%"))
    )
    (comp (ref "R26")
      (value "1K")
      (footprint "eagle-import:R0402")
      (fields
        (field (name "PACKAGE") "0402")
        (field (name "TOLERANCE") "5%")
        (field (name "AEC-Q") "AEC-Q200")
        (field (name "DIGIKEY#") "P1.00KLCT-ND")
        (field (name "MANF") "Panasonic Electronic Components")
        (field (name "MANF#") "ERJ-2RKF1001X")
      )
      (libsource (lib "eagle-import") (part "R-0402-5%"))
    )
    (comp (ref "R27")
      (value "200R")
      (footprint "eagle-import:R0402")
      (fields
        (field (name "PACKAGE") "0402")
        (field (name "TOLERANCE") "5%")
        (field (name "AEC-Q") "AEC-Q200")
        (field (name "DIGIKEY#") "P200JCT-ND")
        (field (name "MANF") "Panasonic Electronic Components")
        (field (name "MANF#") "ERJ-2GEJ201X")
      )
      (libsource (lib "eagle-import") (part "R-0402-5%"))
    )
    (comp (ref "R28")
      (value "4R3")
      (footprint "eagle-import:R0402")
      (fields
        (field (name "PACKAGE") "0402")
        (field (name "TOLERANCE") "1%")
        (field (name "AEC-Q") "1")
        (field (name "DIGIKEY#") "2")
      )
      (libsource (lib "eagle-import") (part "R-0402-1%"))
    )
    (comp (ref "R29")
      (value "4R3")
      (footprint "eagle-import:R0402")
      (fields
        (field (name "PACKAGE") "0402")
        (field (name "TOLERANCE") "1%")
        (field (name "AEC-Q") "1")
        (field (name "DIGIKEY#") "2")
      )
      (libsource (lib "eagle-import") (part "R-0402-1%"))
    )
    (comp (ref "S1")
      (value "SENSE")
      (footprint "eagle-import:SENSE-0.6")
      (libsource (lib "eagle-import") (part "SENSE"))
    )
    (comp (ref "U$1")
      (value "CONNECTION-SMD")
      (footprint "eagle-import:CONNECTION")
      (libsource (lib "eagle-import") (part "CONNECTION-SMD"))
    )
    (comp (ref "U$3")
      (value "CONNECTION-SMD")
      (footprint "eagle-import:CONNECTION")
      (libsource (lib "eagle-import") (part "CONNECTION-SMD"))
    )
    (comp (ref "U$5")
      (value "FIDUCIALMOUNT")
      (footprint "eagle-import:FIDUCIA-MOUNT")
      (libsource (lib "eagle-import") (part "FIDUCIALMOUNT"))
    )
    (comp (ref "U$6")
      (value "FIDUCIALMOUNT")
      (footprint "eagle-import:FIDUCIA-MOUNT")
      (libsource (lib "eagle-import") (part "FIDUCIALMOUNT"))
    )
    (comp (ref "U$7")
      (value "FIDUCIALMOUNT")
      (footprint "eagle-import:FIDUCIA-MOUNT")
      (libsource (lib "eagle-import") (part "FIDUCIALMOUNT"))
    )
    (comp (ref "U$11")
      (value "FIDUCIALMOUNT")
      (footprint "eagle-import:FIDUCIA-MOUNT")
      (libsource (lib "eagle-import") (part "FIDUCIALMOUNT"))
    )
  )
  (nets
    (net (code "1") (name "BEC_ENABLE_OUT") (class "Default")
      (node (ref "IC1") (pin "1") (pinfunction "EN_1") (pintype "bidirectional"))
      (node (ref "IC2") (pin "1") (pinfunction "EN_1") (pintype "bidirectional"))
      (node (ref "MODULE2") (pin "21") (pinfunction "BEC_ENABLE_OUT_21") (pintype "output"))
    )
    (net (code "2") (name "CAN1_LED") (class "Default")
      (node (ref "IC6") (pin "1") (pinfunction "SCIO_1") (pintype "bidirectional"))
      (node (ref "MODULE2") (pin "33") (pinfunction "CAN1_LED_33") (pintype "output"))
      (node (ref "R10") (pin "1") (pinfunction "1_1") (pintype "passive"))
      (node (ref "R26") (pin "1") (pinfunction "1_1") (pintype "passive"))
    )
    (net (code "3") (name "CAN1_RX") (class "Default")
      (node (ref "IC3") (pin "4") (pinfunction "RXD_4") (pintype "bidirectional"))
      (node (ref "MODULE2") (pin "38") (pinfunction "CAN1_RX_38") (pintype "input"))
    )
    (net (code "4") (name "CAN1_TX") (class "Default")
      (node (ref "IC3") (pin "1") (pinfunction "TXD_1") (pintype "bidirectional"))
      (node (ref "MODULE2") (pin "39") (pinfunction "CAN1_TX_39") (pintype "output"))
    )
    (net (code "5") (name "CAN2_RX") (class "Default")
      (node (ref "IC4") (pin "4") (pinfunction "RXD_4") (pintype "bidirectional"))
      (node (ref "MODULE2") (pin "36") (pinfunction "CAN2_RX_36") (pintype "input"))
    )
    (net (code "6") (name "CAN2_TX") (class "Default")
      (node (ref "IC4") (pin "1") (pinfunction "TXD_1") (pintype "bidirectional"))
      (node (ref "MODULE2") (pin "37") (pinfunction "CAN2_TX_37") (pintype "output"))
    )
    (net (code "7") (name "GAIN_OUT") (class "Default")
      (node (ref "LED5") (pin "C") (pinfunction "C_C") (pintype "bidirectional"))
      (node (ref "MODULE2") (pin "22") (pinfunction "GAIN_OUT_22") (pintype "output"))
    )
    (net (code "8") (name "GATE_ENABLE_OUT") (class "Default")
      (node (ref "LED4") (pin "A") (pinfunction "A_A") (pintype "bidirectional"))
      (node (ref "MODULE2") (pin "23") (pinfunction "GATE_ENABLE_OUT_23") (pintype "output"))
    )
    (net (code "9") (name "GND") (class "Default")
      (node (ref "C11") (pin "2") (pinfunction "2_2") (pintype "passive"))
      (node (ref "C12") (pin "2") (pinfunction "2_2") (pintype "passive"))
      (node (ref "C13") (pin "1") (pinfunction "1_1") (pintype "passive"))
      (node (ref "C14") (pin "1") (pinfunction "1_1") (pintype "passive"))
      (node (ref "C15") (pin "1") (pinfunction "1_1") (pintype "passive"))
      (node (ref "C3") (pin "2") (pinfunction "2_2") (pintype "passive"))
      (node (ref "C4") (pin "2") (pinfunction "2_2") (pintype "passive"))
      (node (ref "C45") (pin "2") (pinfunction "2_2") (pintype "passive"))
      (node (ref "CON7") (pin "4") (pinfunction "4_4") (pintype "bidirectional"))
      (node (ref "CON7") (pin "M$0") (pinfunction "GND_M$0") (pintype "bidirectional"))
      (node (ref "CON7") (pin "M$1") (pinfunction "GND_M$1") (pintype "bidirectional"))
      (node (ref "CON8") (pin "1") (pinfunction "1_1") (pintype "passive"))
      (node (ref "CON9") (pin "1") (pinfunction "1_1") (pintype "passive"))
      (node (ref "D4") (pin "1") (pinfunction "C_1") (pintype "bidirectional"))
      (node (ref "D7") (pin "1") (pinfunction "A_1") (pintype "passive"))
      (node (ref "D7") (pin "4") (pinfunction "A_4") (pintype "passive"))
      (node (ref "IC1") (pin "2") (pinfunction "GND_2") (pintype "bidirectional"))
      (node (ref "IC2") (pin "2") (pinfunction "GND_2") (pintype "bidirectional"))
      (node (ref "IC3") (pin "2") (pinfunction "GND_2") (pintype "bidirectional"))
      (node (ref "IC3") (pin "8") (pinfunction "S_8") (pintype "bidirectional"))
      (node (ref "IC3") (pin "PAD") (pinfunction "GND_PAD") (pintype "bidirectional"))
      (node (ref "IC4") (pin "2") (pinfunction "GND_2") (pintype "bidirectional"))
      (node (ref "IC4") (pin "8") (pinfunction "S_8") (pintype "bidirectional"))
      (node (ref "IC4") (pin "PAD") (pinfunction "GND_PAD") (pintype "bidirectional"))
      (node (ref "IC5") (pin "3") (pinfunction "GND_3") (pintype "bidirectional"))
      (node (ref "IC6") (pin "3") (pinfunction "VSS_3") (pintype "bidirectional"))
      (node (ref "J1") (pin "5") (pinfunction "GND_5") (pintype "passive"))
      (node (ref "J1") (pin "S1") (pinfunction "SHIELD_S1") (pintype "passive"))
      (node (ref "J1") (pin "S2") (pinfunction "SHIELD_S2") (pintype "passive"))
      (node (ref "J1") (pin "S3") (pinfunction "SHIELD_S3") (pintype "passive"))
      (node (ref "LED4") (pin "C") (pinfunction "C_C") (pintype "bidirectional"))
      (node (ref "MODULE2") (pin "41") (pinfunction "GND_41") (pintype "power_in"))
      (node (ref "R7") (pin "2") (pinfunction "2_2") (pintype "passive"))
      (node (ref "U$1") (pin "P$1") (pinfunction "P$1_P$1") (pintype "bidirectional"))
      (node (ref "U$3") (pin "P$1") (pinfunction "P$1_P$1") (pintype "bidirectional"))
    )
    (net (code "10") (name "GNDD") (class "Default")
      (node (ref "C10") (pin "1") (pinfunction "1_1") (pintype "passive"))
      (node (ref "C5") (pin "1") (pinfunction "1_1") (pintype "passive"))
      (node (ref "C6") (pin "1") (pinfunction "1_1") (pintype "passive"))
      (node (ref "C7") (pin "1") (pinfunction "1_1") (pintype "passive"))
      (node (ref "C8") (pin "1") (pinfunction "1_1") (pintype "passive"))
      (node (ref "C9") (pin "1") (pinfunction "1_1") (pintype "passive"))
      (node (ref "CON3") (pin "4") (pinfunction "4_4") (pintype "bidirectional"))
      (node (ref "CON3") (pin "M$0") (pinfunction "GND_M$0") (pintype "bidirectional"))
      (node (ref "CON3") (pin "M$1") (pinfunction "GND_M$1") (pintype "bidirectional"))
      (node (ref "CON4") (pin "4") (pinfunction "4_4") (pintype "bidirectional"))
      (node (ref "CON4") (pin "M$0") (pinfunction "GND_M$0") (pintype "bidirectional"))
      (node (ref "CON4") (pin "M$1") (pinfunction "GND_M$1") (pintype "bidirectional"))
      (node (ref "CON5") (pin "4") (pinfunction "4_4") (pintype "bidirectional"))
      (node (ref "CON5") (pin "M$0") (pinfunction "GND_M$0") (pintype "bidirectional"))
      (node (ref "CON5") (pin "M$1") (pinfunction "GND_M$1") (pintype "bidirectional"))
      (node (ref "CON6") (pin "4") (pinfunction "4_4") (pintype "bidirectional"))
      (node (ref "CON6") (pin "M$0") (pinfunction "GND_M$0") (pintype "bidirectional"))
      (node (ref "CON6") (pin "M$1") (pinfunction "GND_M$1") (pintype "bidirectional"))
      (node (ref "U$1") (pin "P$2") (pinfunction "P$2_P$2") (pintype "bidirectional"))
    )
    (net (code "11") (name "GPIO1") (class "Default")
      (node (ref "CON2") (pin "1") (pinfunction "1_1") (pintype "passive"))
      (node (ref "D7") (pin "6") (pinfunction "COMMON_6") (pintype "bidirectional"))
      (node (ref "MODULE2") (pin "25") (pinfunction "GPIO1_25") (pintype "bidirectional"))
      (node (ref "R8") (pin "1") (pinfunction "1_1") (pintype "passive"))
    )
    (net (code "12") (name "GPIO2") (class "Default")
      (node (ref "D7") (pin "3") (pinfunction "COMMON_3") (pintype "bidirectional"))
      (node (ref "MODULE2") (pin "24") (pinfunction "GPIO2_24") (pintype "bidirectional"))
      (node (ref "R25") (pin "1") (pinfunction "1_1") (pintype "passive"))
    )
    (net (code "13") (name "Net-(CON7-Pad2)") (class "Default")
      (node (ref "CON7") (pin "2") (pinfunction "2_2") (pintype "bidirectional"))
      (node (ref "R8") (pin "2") (pinfunction "2_2") (pintype "passive"))
    )
    (net (code "14") (name "Net-(CON7-Pad3)") (class "Default")
      (node (ref "CON7") (pin "3") (pinfunction "3_3") (pintype "bidirectional"))
      (node (ref "R25") (pin "2") (pinfunction "2_2") (pintype "passive"))
    )
    (net (code "15") (name "Net-(CON8-Pad2)") (class "Default")
      (node (ref "CON8") (pin "2") (pinfunction "2_2") (pintype "passive"))
      (node (ref "R29") (pin "1") (pinfunction "1_1") (pintype "passive"))
    )
    (net (code "16") (name "Net-(CON8-Pad3)") (class "Default")
      (node (ref "CON8") (pin "3") (pinfunction "3_3") (pintype "passive"))
      (node (ref "R28") (pin "1") (pinfunction "1_1") (pintype "passive"))
    )
    (net (code "17") (name "Net-(D4-A)") (class "Default")
      (node (ref "D2") (pin "A") (pinfunction "A_A") (pintype "passive"))
      (node (ref "D4") (pin "4") (pinfunction "A_4") (pintype "bidirectional"))
      (node (ref "J1") (pin "1") (pinfunction "VBUS_1") (pintype "passive"))
      (node (ref "R6") (pin "2") (pinfunction "2_2") (pintype "passive"))
    )
    (net (code "18") (name "Net-(D4-D1)") (class "Default")
      (node (ref "D4") (pin "2") (pinfunction "D1_2") (pintype "bidirectional"))
      (node (ref "MODULE2") (pin "32") (pinfunction "USB+_32") (pintype "bidirectional"))
      (node (ref "R19") (pin "1") (pinfunction "1_1") (pintype "passive"))
    )
    (net (code "19") (name "Net-(D4-D2)") (class "Default")
      (node (ref "D4") (pin "3") (pinfunction "D2_3") (pintype "bidirectional"))
      (node (ref "MODULE2") (pin "31") (pinfunction "USB-_31") (pintype "bidirectional"))
      (node (ref "R20") (pin "1") (pinfunction "1_1") (pintype "passive"))
    )
    (net (code "20") (name "Net-(F1-1)") (class "Default")
      (node (ref "CON7") (pin "1") (pinfunction "1_1") (pintype "bidirectional"))
      (node (ref "F1") (pin "P$1") (pinfunction "1_P$1") (pintype "passive"))
    )
    (net (code "21") (name "Net-(IC1-OUT)") (class "Default")
      (node (ref "C5") (pin "2") (pinfunction "2_2") (pintype "passive"))
      (node (ref "C7") (pin "2") (pinfunction "2_2") (pintype "passive"))
      (node (ref "C9") (pin "2") (pinfunction "2_2") (pintype "passive"))
      (node (ref "CON3") (pin "1") (pinfunction "1_1") (pintype "bidirectional"))
      (node (ref "CON4") (pin "1") (pinfunction "1_1") (pintype "bidirectional"))
      (node (ref "IC1") (pin "4") (pinfunction "OUT_4") (pintype "bidirectional"))
    )
    (net (code "22") (name "Net-(IC2-OUT)") (class "Default")
      (node (ref "C10") (pin "2") (pinfunction "2_2") (pintype "passive"))
      (node (ref "C6") (pin "2") (pinfunction "2_2") (pintype "passive"))
      (node (ref "C8") (pin "2") (pinfunction "2_2") (pintype "passive"))
      (node (ref "CON5") (pin "1") (pinfunction "1_1") (pintype "bidirectional"))
      (node (ref "CON6") (pin "1") (pinfunction "1_1") (pintype "bidirectional"))
      (node (ref "IC2") (pin "4") (pinfunction "OUT_4") (pintype "bidirectional"))
    )
    (net (code "23") (name "Net-(IC3-CANH)") (class "Default")
      (node (ref "CON3") (pin "2") (pinfunction "2_2") (pintype "bidirectional"))
      (node (ref "CON4") (pin "2") (pinfunction "2_2") (pintype "bidirectional"))
      (node (ref "IC3") (pin "7") (pinfunction "CANH_7") (pintype "bidirectional"))
    )
    (net (code "24") (name "Net-(IC3-CANL)") (class "Default")
      (node (ref "CON3") (pin "3") (pinfunction "3_3") (pintype "bidirectional"))
      (node (ref "CON4") (pin "3") (pinfunction "3_3") (pintype "bidirectional"))
      (node (ref "IC3") (pin "6") (pinfunction "CANL_6") (pintype "bidirectional"))
    )
    (net (code "25") (name "Net-(IC4-CANH)") (class "Default")
      (node (ref "CON5") (pin "2") (pinfunction "2_2") (pintype "bidirectional"))
      (node (ref "CON6") (pin "2") (pinfunction "2_2") (pintype "bidirectional"))
      (node (ref "IC4") (pin "7") (pinfunction "CANH_7") (pintype "bidirectional"))
    )
    (net (code "26") (name "Net-(IC4-CANL)") (class "Default")
      (node (ref "CON5") (pin "3") (pinfunction "3_3") (pintype "bidirectional"))
      (node (ref "CON6") (pin "3") (pinfunction "3_3") (pintype "bidirectional"))
      (node (ref "IC4") (pin "6") (pinfunction "CANL_6") (pintype "bidirectional"))
    )
    (net (code "27") (name "Net-(IC5-VCC)") (class "Default")
      (node (ref "C14") (pin "2") (pinfunction "2_2") (pintype "passive"))
      (node (ref "IC5") (pin "1") (pinfunction "VCC_1") (pintype "bidirectional"))
      (node (ref "R27") (pin "1") (pinfunction "1_1") (pintype "passive"))
    )
    (net (code "28") (name "Net-(J1-D+)") (class "Default")
      (node (ref "J1") (pin "3") (pinfunction "D+_3") (pintype "passive"))
      (node (ref "R19") (pin "2") (pinfunction "2_2") (pintype "passive"))
    )
    (net (code "29") (name "Net-(J1-D-)") (class "Default")
      (node (ref "J1") (pin "2") (pinfunction "D-_2") (pintype "passive"))
      (node (ref "R20") (pin "2") (pinfunction "2_2") (pintype "passive"))
    )
    (net (code "30") (name "Net-(LED1-PadC)") (class "Default")
      (node (ref "LED1") (pin "C") (pinfunction "C_C") (pintype "bidirectional"))
      (node (ref "R9") (pin "2") (pinfunction "2_2") (pintype "passive"))
    )
    (net (code "31") (name "Net-(LED2-PadC)") (class "Default")
      (node (ref "LED2") (pin "C") (pinfunction "C_C") (pintype "bidirectional"))
      (node (ref "R10") (pin "2") (pinfunction "2_2") (pintype "passive"))
    )
    (net (code "32") (name "Net-(LED3-PadB)") (class "Default")
      (node (ref "LED3") (pin "B") (pinfunction "B_B") (pintype "bidirectional"))
      (node (ref "R11") (pin "1") (pinfunction "1_1") (pintype "passive"))
    )
    (net (code "33") (name "Net-(LED3-PadG)") (class "Default")
      (node (ref "LED3") (pin "G") (pinfunction "G_G") (pintype "bidirectional"))
      (node (ref "R12") (pin "1") (pinfunction "1_1") (pintype "passive"))
    )
    (net (code "34") (name "Net-(LED3-PadR)") (class "Default")
      (node (ref "LED3") (pin "R") (pinfunction "R_R") (pintype "bidirectional"))
      (node (ref "R13") (pin "1") (pinfunction "1_1") (pintype "passive"))
    )
    (net (code "35") (name "Net-(MODULE2-CAN2_LED)") (class "Default")
      (node (ref "MODULE2") (pin "34") (pinfunction "CAN2_LED_34") (pintype "output"))
      (node (ref "R9") (pin "1") (pinfunction "1_1") (pintype "passive"))
    )
    (net (code "36") (name "Net-(MODULE2-OVERCURRENT_PROTECT_ADJ)") (class "Default")
      (node (ref "MODULE2") (pin "26") (pinfunction "OVERCURRENT_PROTECT_ADJ_26") (pintype "input"))
      (node (ref "R7") (pin "1") (pinfunction "1_1") (pintype "passive"))
    )
    (net (code "37") (name "Net-(MODULE2-RGB_LED_B)") (class "Default")
      (node (ref "MODULE2") (pin "29") (pinfunction "RGB_LED_B_29") (pintype "output"))
      (node (ref "R11") (pin "2") (pinfunction "2_2") (pintype "passive"))
    )
    (net (code "38") (name "Net-(MODULE2-RGB_LED_G)") (class "Default")
      (node (ref "MODULE2") (pin "28") (pinfunction "RGB_LED_G_28") (pintype "output"))
      (node (ref "R12") (pin "2") (pinfunction "2_2") (pintype "passive"))
    )
    (net (code "39") (name "Net-(MODULE2-RGB_LED_R)") (class "Default")
      (node (ref "MODULE2") (pin "27") (pinfunction "RGB_LED_R_27") (pintype "output"))
      (node (ref "R13") (pin "2") (pinfunction "2_2") (pintype "passive"))
    )
    (net (code "40") (name "Net-(MODULE2-USB_VBUS)") (class "Default")
      (node (ref "MODULE2") (pin "30") (pinfunction "USB_VBUS_30") (pintype "input"))
      (node (ref "R6") (pin "1") (pinfunction "1_1") (pintype "passive"))
    )
    (net (code "41") (name "Net-(Q1-G)") (class "Default")
      (node (ref "Q1") (pin "4") (pinfunction "G_4") (pintype "passive"))
      (node (ref "R2") (pin "2") (pinfunction "2_2") (pintype "passive"))
    )
    (net (code "42") (name "Net-(Q2-G)") (class "Default")
      (node (ref "Q2") (pin "4") (pinfunction "G_4") (pintype "passive"))
      (node (ref "R3") (pin "2") (pinfunction "2_2") (pintype "passive"))
    )
    (net (code "43") (name "Net-(Q3-G)") (class "Default")
      (node (ref "Q3") (pin "4") (pinfunction "G_4") (pintype "passive"))
      (node (ref "R1") (pin "2") (pinfunction "2_2") (pintype "passive"))
    )
    (net (code "44") (name "Net-(Q4-G)") (class "Default")
      (node (ref "Q4") (pin "4") (pinfunction "G_4") (pintype "passive"))
      (node (ref "R4") (pin "2") (pinfunction "2_2") (pintype "passive"))
    )
    (net (code "45") (name "Net-(Q5-G)") (class "Default")
      (node (ref "Q5") (pin "4") (pinfunction "G_4") (pintype "passive"))
      (node (ref "R15") (pin "2") (pinfunction "2_2") (pintype "passive"))
    )
    (net (code "46") (name "Net-(Q6-G)") (class "Default")
      (node (ref "Q6") (pin "4") (pinfunction "G_4") (pintype "passive"))
      (node (ref "R16") (pin "2") (pinfunction "2_2") (pintype "passive"))
    )
    (net (code "47") (name "Net-(Q7-G)") (class "Default")
      (node (ref "Q7") (pin "4") (pinfunction "G_4") (pintype "passive"))
      (node (ref "R14") (pin "2") (pinfunction "2_2") (pintype "passive"))
    )
    (net (code "48") (name "Net-(Q8-G)") (class "Default")
      (node (ref "Q8") (pin "4") (pinfunction "G_4") (pintype "passive"))
      (node (ref "R17") (pin "2") (pinfunction "2_2") (pintype "passive"))
    )
    (net (code "49") (name "Net-(Q9-G)") (class "Default")
      (node (ref "Q9") (pin "4") (pinfunction "G_4") (pintype "passive"))
      (node (ref "R22") (pin "2") (pinfunction "2_2") (pintype "passive"))
    )
    (net (code "50") (name "Net-(Q10-G)") (class "Default")
      (node (ref "Q10") (pin "4") (pinfunction "G_4") (pintype "passive"))
      (node (ref "R23") (pin "2") (pinfunction "2_2") (pintype "passive"))
    )
    (net (code "51") (name "Net-(Q11-G)") (class "Default")
      (node (ref "Q11") (pin "4") (pinfunction "G_4") (pintype "passive"))
      (node (ref "R21") (pin "2") (pinfunction "2_2") (pintype "passive"))
    )
    (net (code "52") (name "Net-(Q12-G)") (class "Default")
      (node (ref "Q12") (pin "4") (pinfunction "G_4") (pintype "passive"))
      (node (ref "R24") (pin "2") (pinfunction "2_2") (pintype "passive"))
    )
    (net (code "53") (name "PGND") (class "Default")
      (node (ref "C1") (pin "-") (pinfunction "-_-") (pintype "passive"))
      (node (ref "C2") (pin "-") (pinfunction "-_-") (pintype "passive"))
      (node (ref "C24") (pin "1") (pinfunction "1_1") (pintype "passive"))
      (node (ref "C31") (pin "1") (pinfunction "1_1") (pintype "passive"))
      (node (ref "C32") (pin "1") (pinfunction "1_1") (pintype "passive"))
      (node (ref "C35") (pin "1") (pinfunction "1_1") (pintype "passive"))
      (node (ref "C58") (pin "1") (pinfunction "1_1") (pintype "passive"))
      (node (ref "C62") (pin "1") (pinfunction "1_1") (pintype "passive"))
      (node (ref "C63") (pin "1") (pinfunction "1_1") (pintype "passive"))
      (node (ref "C64") (pin "1") (pinfunction "1_1") (pintype "passive"))
      (node (ref "C66") (pin "1") (pinfunction "1_1") (pintype "passive"))
      (node (ref "D1") (pin "A") (pinfunction "A_A") (pintype "passive"))
      (node (ref "D5") (pin "A") (pinfunction "A_A") (pintype "passive"))
      (node (ref "D6") (pin "A") (pinfunction "A_A") (pintype "passive"))
      (node (ref "PAD4") (pin "1") (pinfunction "P$1_1") (pintype "bidirectional"))
      (node (ref "Q10") (pin "1") (pinfunction "S_1") (pintype "passive"))
      (node (ref "Q10") (pin "2") (pinfunction "S_2") (pintype "passive"))
      (node (ref "Q10") (pin "3") (pinfunction "S_3") (pintype "passive"))
      (node (ref "Q12") (pin "1") (pinfunction "S_1") (pintype "passive"))
      (node (ref "Q12") (pin "2") (pinfunction "S_2") (pintype "passive"))
      (node (ref "Q12") (pin "3") (pinfunction "S_3") (pintype "passive"))
      (node (ref "R18") (pin "2") (pinfunction "2_2") (pintype "bidirectional"))
      (node (ref "R18") (pin "22") (pinfunction "2_22") (pintype "bidirectional"))
      (node (ref "R5") (pin "2") (pinfunction "2_2") (pintype "bidirectional"))
      (node (ref "R5") (pin "22") (pinfunction "2_22") (pintype "bidirectional"))
      (node (ref "S1") (pin "SHELL") (pinfunction "SHELLL_SHELL") (pintype "bidirectional"))
      (node (ref "U$3") (pin "P$2") (pinfunction "P$2_P$2") (pintype "bidirectional"))
    )
    (net (code "54") (name "PHASE_A") (class "Default")
      (node (ref "MODULE2") (pin "2") (pinfunction "PHASE_A_2") (pintype "input"))
      (node (ref "PAD2") (pin "1") (pinfunction "P$1_1") (pintype "bidirectional"))
      (node (ref "Q5") (pin "1") (pinfunction "S_1") (pintype "passive"))
      (node (ref "Q5") (pin "2") (pinfunction "S_2") (pintype "passive"))
      (node (ref "Q5") (pin "3") (pinfunction "S_3") (pintype "passive"))
      (node (ref "Q6") (pin "5") (pinfunction "D_5") (pintype "passive"))
      (node (ref "Q6") (pin "6") (pinfunction "D_6") (pintype "passive"))
      (node (ref "Q6") (pin "7") (pinfunction "D_7") (pintype "passive"))
      (node (ref "Q6") (pin "8") (pinfunction "D_8") (pintype "passive"))
      (node (ref "Q6") (pin "P$1") (pinfunction "D_P$1") (pintype "passive"))
      (node (ref "Q7") (pin "1") (pinfunction "S_1") (pintype "passive"))
      (node (ref "Q7") (pin "2") (pinfunction "S_2") (pintype "passive"))
      (node (ref "Q7") (pin "3") (pinfunction "S_3") (pintype "passive"))
      (node (ref "Q8") (pin "5") (pinfunction "D_5") (pintype "passive"))
      (node (ref "Q8") (pin "6") (pinfunction "D_6") (pintype "passive"))
      (node (ref "Q8") (pin "7") (pinfunction "D_7") (pintype "passive"))
      (node (ref "Q8") (pin "8") (pinfunction "D_8") (pintype "passive"))
      (node (ref "Q8") (pin "P$1") (pinfunction "D_P$1") (pintype "passive"))
    )
    (net (code "55") (name "PHASE_A_CURRENT_SHUNT_N") (class "Default")
      (node (ref "MODULE2") (pin "13") (pinfunction "PHASE_A_CURRENT_SHUNT_N_13") (pintype "input"))
      (node (ref "R18") (pin "S1") (pinfunction "S1_S1") (pintype "bidirectional"))
    )
    (net (code "56") (name "PHASE_A_CURRENT_SHUNT_P") (class "Default")
      (node (ref "MODULE2") (pin "14") (pinfunction "PHASE_A_CURRENT_SHUNT_P_14") (pintype "input"))
      (node (ref "R18") (pin "S2") (pinfunction "S2_S2") (pintype "bidirectional"))
    )
    (net (code "57") (name "PHASE_A_GATE_HIGH") (class "Default")
      (node (ref "MODULE2") (pin "1") (pinfunction "PHASE_A_GATE_HIGH_1") (pintype "output"))
      (node (ref "R14") (pin "1") (pinfunction "1_1") (pintype "passive"))
      (node (ref "R15") (pin "1") (pinfunction "1_1") (pintype "passive"))
    )
    (net (code "58") (name "PHASE_A_GATE_LOW") (class "Default")
      (node (ref "MODULE2") (pin "3") (pinfunction "PHASE_A_GATE_LOW_3") (pintype "output"))
      (node (ref "R16") (pin "1") (pinfunction "1_1") (pintype "passive"))
      (node (ref "R17") (pin "1") (pinfunction "1_1") (pintype "passive"))
    )
    (net (code "59") (name "PHASE_A_GND") (class "Default")
      (node (ref "MODULE2") (pin "4") (pinfunction "PHASE_A_GND_4") (pintype "input"))
      (node (ref "Q6") (pin "1") (pinfunction "S_1") (pintype "passive"))
      (node (ref "Q6") (pin "2") (pinfunction "S_2") (pintype "passive"))
      (node (ref "Q6") (pin "3") (pinfunction "S_3") (pintype "passive"))
      (node (ref "Q8") (pin "1") (pinfunction "S_1") (pintype "passive"))
      (node (ref "Q8") (pin "2") (pinfunction "S_2") (pintype "passive"))
      (node (ref "Q8") (pin "3") (pinfunction "S_3") (pintype "passive"))
      (node (ref "R18") (pin "1") (pinfunction "1_1") (pintype "bidirectional"))
      (node (ref "R18") (pin "11") (pinfunction "1_11") (pintype "bidirectional"))
    )
    (net (code "60") (name "PHASE_B") (class "Default")
      (node (ref "MODULE2") (pin "6") (pinfunction "PHASE_B_6") (pintype "input"))
      (node (ref "PAD1") (pin "1") (pinfunction "P$1_1") (pintype "bidirectional"))
      (node (ref "Q1") (pin "1") (pinfunction "S_1") (pintype "passive"))
      (node (ref "Q1") (pin "2") (pinfunction "S_2") (pintype "passive"))
      (node (ref "Q1") (pin "3") (pinfunction "S_3") (pintype "passive"))
      (node (ref "Q2") (pin "5") (pinfunction "D_5") (pintype "passive"))
      (node (ref "Q2") (pin "6") (pinfunction "D_6") (pintype "passive"))
      (node (ref "Q2") (pin "7") (pinfunction "D_7") (pintype "passive"))
      (node (ref "Q2") (pin "8") (pinfunction "D_8") (pintype "passive"))
      (node (ref "Q2") (pin "P$1") (pinfunction "D_P$1") (pintype "passive"))
      (node (ref "Q3") (pin "1") (pinfunction "S_1") (pintype "passive"))
      (node (ref "Q3") (pin "2") (pinfunction "S_2") (pintype "passive"))
      (node (ref "Q3") (pin "3") (pinfunction "S_3") (pintype "passive"))
      (node (ref "Q4") (pin "5") (pinfunction "D_5") (pintype "passive"))
      (node (ref "Q4") (pin "6") (pinfunction "D_6") (pintype "passive"))
      (node (ref "Q4") (pin "7") (pinfunction "D_7") (pintype "passive"))
      (node (ref "Q4") (pin "8") (pinfunction "D_8") (pintype "passive"))
      (node (ref "Q4") (pin "P$1") (pinfunction "D_P$1") (pintype "passive"))
    )
    (net (code "61") (name "PHASE_B_CURRENT_SHUNT_N") (class "Default")
      (node (ref "MODULE2") (pin "15") (pinfunction "PHASE_B_CURRENT_SHUNT_N_15") (pintype "input"))
      (node (ref "R5") (pin "S1") (pinfunction "S1_S1") (pintype "bidirectional"))
    )
    (net (code "62") (name "PHASE_B_CURRENT_SHUNT_P") (class "Default")
      (node (ref "MODULE2") (pin "16") (pinfunction "PHASE_B_CURRENT_SHUNT_P_16") (pintype "input"))
      (node (ref "R5") (pin "S2") (pinfunction "S2_S2") (pintype "bidirectional"))
    )
    (net (code "63") (name "PHASE_B_GATE_HIGH") (class "Default")
      (node (ref "MODULE2") (pin "5") (pinfunction "PHASE_B_GATE_HIGH_5") (pintype "output"))
      (node (ref "R1") (pin "1") (pinfunction "1_1") (pintype "passive"))
      (node (ref "R2") (pin "1") (pinfunction "1_1") (pintype "passive"))
    )
    (net (code "64") (name "PHASE_B_GATE_LOW") (class "Default")
      (node (ref "MODULE2") (pin "7") (pinfunction "PHASE_B_GATE_LOW_7") (pintype "output"))
      (node (ref "R3") (pin "1") (pinfunction "1_1") (pintype "passive"))
      (node (ref "R4") (pin "1") (pinfunction "1_1") (pintype "passive"))
    )
    (net (code "65") (name "PHASE_B_GND") (class "Default")
      (node (ref "MODULE2") (pin "8") (pinfunction "PHASE_B_GND_8") (pintype "input"))
      (node (ref "Q2") (pin "1") (pinfunction "S_1") (pintype "passive"))
      (node (ref "Q2") (pin "2") (pinfunction "S_2") (pintype "passive"))
      (node (ref "Q2") (pin "3") (pinfunction "S_3") (pintype "passive"))
      (node (ref "Q4") (pin "1") (pinfunction "S_1") (pintype "passive"))
      (node (ref "Q4") (pin "2") (pinfunction "S_2") (pintype "passive"))
      (node (ref "Q4") (pin "3") (pinfunction "S_3") (pintype "passive"))
      (node (ref "R5") (pin "1") (pinfunction "1_1") (pintype "bidirectional"))
      (node (ref "R5") (pin "11") (pinfunction "1_11") (pintype "bidirectional"))
    )
    (net (code "66") (name "PHASE_C") (class "Default")
      (node (ref "MODULE2") (pin "10") (pinfunction "PHASE_C_10") (pintype "input"))
      (node (ref "PAD3") (pin "1") (pinfunction "P$1_1") (pintype "bidirectional"))
      (node (ref "Q10") (pin "5") (pinfunction "D_5") (pintype "passive"))
      (node (ref "Q10") (pin "6") (pinfunction "D_6") (pintype "passive"))
      (node (ref "Q10") (pin "7") (pinfunction "D_7") (pintype "passive"))
      (node (ref "Q10") (pin "8") (pinfunction "D_8") (pintype "passive"))
      (node (ref "Q10") (pin "P$1") (pinfunction "D_P$1") (pintype "passive"))
      (node (ref "Q11") (pin "1") (pinfunction "S_1") (pintype "passive"))
      (node (ref "Q11") (pin "2") (pinfunction "S_2") (pintype "passive"))
      (node (ref "Q11") (pin "3") (pinfunction "S_3") (pintype "passive"))
      (node (ref "Q12") (pin "5") (pinfunction "D_5") (pintype "passive"))
      (node (ref "Q12") (pin "6") (pinfunction "D_6") (pintype "passive"))
      (node (ref "Q12") (pin "7") (pinfunction "D_7") (pintype "passive"))
      (node (ref "Q12") (pin "8") (pinfunction "D_8") (pintype "passive"))
      (node (ref "Q12") (pin "P$1") (pinfunction "D_P$1") (pintype "passive"))
      (node (ref "Q9") (pin "1") (pinfunction "S_1") (pintype "passive"))
      (node (ref "Q9") (pin "2") (pinfunction "S_2") (pintype "passive"))
      (node (ref "Q9") (pin "3") (pinfunction "S_3") (pintype "passive"))
    )
    (net (code "67") (name "PHASE_C_GATE_HIGH") (class "Default")
      (node (ref "MODULE2") (pin "9") (pinfunction "PHASE_C_GATE_HIGH_9") (pintype "output"))
      (node (ref "R21") (pin "1") (pinfunction "1_1") (pintype "passive"))
      (node (ref "R22") (pin "1") (pinfunction "1_1") (pintype "passive"))
    )
    (net (code "68") (name "PHASE_C_GATE_LOW") (class "Default")
      (node (ref "MODULE2") (pin "11") (pinfunction "PHASE_C_GATE_LOW_11") (pintype "output"))
      (node (ref "R23") (pin "1") (pinfunction "1_1") (pintype "passive"))
      (node (ref "R24") (pin "1") (pinfunction "1_1") (pintype "passive"))
    )
    (net (code "69") (name "PHASE_C_GND") (class "Default")
      (node (ref "MODULE2") (pin "12") (pinfunction "PHASE_C_GND_12") (pintype "input"))
      (node (ref "S1") (pin "IN") (pinfunction "IN_IN") (pintype "bidirectional"))
    )
    (net (code "70") (name "TEMPERATURE_SENSOR") (class "Default")
      (node (ref "C13") (pin "2") (pinfunction "2_2") (pintype "passive"))
      (node (ref "IC5") (pin "2") (pinfunction "OUT_2") (pintype "bidirectional"))
      (node (ref "MODULE2") (pin "17") (pinfunction "TEMPERATURE_SENSOR_17") (pintype "input"))
    )
    (net (code "71") (name "UART_RX") (class "Default")
      (node (ref "MODULE2") (pin "20") (pinfunction "UART_RX_20") (pintype "input"))
      (node (ref "R29") (pin "2") (pinfunction "2_2") (pintype "passive"))
    )
    (net (code "72") (name "UART_TX") (class "Default")
      (node (ref "MODULE2") (pin "19") (pinfunction "UART_TX_19") (pintype "output"))
      (node (ref "R28") (pin "2") (pinfunction "2_2") (pintype "passive"))
    )
    (net (code "73") (name "VDC") (class "Default")
      (node (ref "C1") (pin "+") (pinfunction "+_+") (pintype "passive"))
      (node (ref "C2") (pin "+") (pinfunction "+_+") (pintype "passive"))
      (node (ref "C24") (pin "2") (pinfunction "2_2") (pintype "passive"))
      (node (ref "C31") (pin "2") (pinfunction "2_2") (pintype "passive"))
      (node (ref "C32") (pin "2") (pinfunction "2_2") (pintype "passive"))
      (node (ref "C35") (pin "2") (pinfunction "2_2") (pintype "passive"))
      (node (ref "C58") (pin "2") (pinfunction "2_2") (pintype "passive"))
      (node (ref "C62") (pin "2") (pinfunction "2_2") (pintype "passive"))
      (node (ref "C63") (pin "2") (pinfunction "2_2") (pintype "passive"))
      (node (ref "C64") (pin "2") (pinfunction "2_2") (pintype "passive"))
      (node (ref "C66") (pin "2") (pinfunction "2_2") (pintype "passive"))
      (node (ref "D1") (pin "C") (pinfunction "C_C") (pintype "passive"))
      (node (ref "D5") (pin "C") (pinfunction "C_C") (pintype "passive"))
      (node (ref "D6") (pin "C") (pinfunction "C_C") (pintype "passive"))
      (node (ref "MODULE2") (pin "42") (pinfunction "VDC_42") (pintype "power_in"))
      (node (ref "PAD5") (pin "1") (pinfunction "P$1_1") (pintype "bidirectional"))
      (node (ref "Q1") (pin "5") (pinfunction "D_5") (pintype "passive"))
      (node (ref "Q1") (pin "6") (pinfunction "D_6") (pintype "passive"))
      (node (ref "Q1") (pin "7") (pinfunction "D_7") (pintype "passive"))
      (node (ref "Q1") (pin "8") (pinfunction "D_8") (pintype "passive"))
      (node (ref "Q1") (pin "P$1") (pinfunction "D_P$1") (pintype "passive"))
      (node (ref "Q11") (pin "5") (pinfunction "D_5") (pintype "passive"))
      (node (ref "Q11") (pin "6") (pinfunction "D_6") (pintype "passive"))
      (node (ref "Q11") (pin "7") (pinfunction "D_7") (pintype "passive"))
      (node (ref "Q11") (pin "8") (pinfunction "D_8") (pintype "passive"))
      (node (ref "Q11") (pin "P$1") (pinfunction "D_P$1") (pintype "passive"))
      (node (ref "Q3") (pin "5") (pinfunction "D_5") (pintype "passive"))
      (node (ref "Q3") (pin "6") (pinfunction "D_6") (pintype "passive"))
      (node (ref "Q3") (pin "7") (pinfunction "D_7") (pintype "passive"))
      (node (ref "Q3") (pin "8") (pinfunction "D_8") (pintype "passive"))
      (node (ref "Q3") (pin "P$1") (pinfunction "D_P$1") (pintype "passive"))
      (node (ref "Q5") (pin "5") (pinfunction "D_5") (pintype "passive"))
      (node (ref "Q5") (pin "6") (pinfunction "D_6") (pintype "passive"))
      (node (ref "Q5") (pin "7") (pinfunction "D_7") (pintype "passive"))
      (node (ref "Q5") (pin "8") (pinfunction "D_8") (pintype "passive"))
      (node (ref "Q5") (pin "P$1") (pinfunction "D_P$1") (pintype "passive"))
      (node (ref "Q7") (pin "5") (pinfunction "D_5") (pintype "passive"))
      (node (ref "Q7") (pin "6") (pinfunction "D_6") (pintype "passive"))
      (node (ref "Q7") (pin "7") (pinfunction "D_7") (pintype "passive"))
      (node (ref "Q7") (pin "8") (pinfunction "D_8") (pintype "passive"))
      (node (ref "Q7") (pin "P$1") (pinfunction "D_P$1") (pintype "passive"))
      (node (ref "Q9") (pin "5") (pinfunction "D_5") (pintype "passive"))
      (node (ref "Q9") (pin "6") (pinfunction "D_6") (pintype "passive"))
      (node (ref "Q9") (pin "7") (pinfunction "D_7") (pintype "passive"))
      (node (ref "Q9") (pin "8") (pinfunction "D_8") (pintype "passive"))
      (node (ref "Q9") (pin "P$1") (pinfunction "D_P$1") (pintype "passive"))
    )
    (net (code "74") (name "VDD_5V") (class "Default")
      (node (ref "C11") (pin "1") (pinfunction "1_1") (pintype "passive"))
      (node (ref "C12") (pin "1") (pinfunction "1_1") (pintype "passive"))
      (node (ref "C15") (pin "2") (pinfunction "2_2") (pintype "passive"))
      (node (ref "C3") (pin "1") (pinfunction "1_1") (pintype "passive"))
      (node (ref "C4") (pin "1") (pinfunction "1_1") (pintype "passive"))
      (node (ref "C45") (pin "1") (pinfunction "1_1") (pintype "passive"))
      (node (ref "CON8") (pin "4") (pinfunction "4_4") (pintype "passive"))
      (node (ref "D2") (pin "C") (pinfunction "C_C") (pintype "passive"))
      (node (ref "D7") (pin "2") (pinfunction "C_2") (pintype "passive"))
      (node (ref "D7") (pin "5") (pinfunction "C_5") (pintype "passive"))
      (node (ref "F1") (pin "P$2") (pinfunction "2_P$2") (pintype "passive"))
      (node (ref "IC1") (pin "3") (pinfunction "IN_3") (pintype "bidirectional"))
      (node (ref "IC2") (pin "3") (pinfunction "IN_3") (pintype "bidirectional"))
      (node (ref "IC3") (pin "3") (pinfunction "VCC_3") (pintype "bidirectional"))
      (node (ref "IC3") (pin "5") (pinfunction "VIO_5") (pintype "bidirectional"))
      (node (ref "IC4") (pin "3") (pinfunction "VCC_3") (pintype "bidirectional"))
      (node (ref "IC4") (pin "5") (pinfunction "VIO_5") (pintype "bidirectional"))
      (node (ref "IC6") (pin "2") (pinfunction "VCC_2") (pintype "bidirectional"))
      (node (ref "LED1") (pin "A") (pinfunction "A_A") (pintype "bidirectional"))
      (node (ref "LED2") (pin "A") (pinfunction "A_A") (pintype "bidirectional"))
      (node (ref "LED3") (pin "+") (pinfunction "A_+") (pintype "bidirectional"))
      (node (ref "LED5") (pin "A") (pinfunction "A_A") (pintype "bidirectional"))
      (node (ref "MODULE2") (pin "40") (pinfunction "5V_OUT_40") (pintype "power_in"))
      (node (ref "R26") (pin "2") (pinfunction "2_2") (pintype "passive"))
      (node (ref "R27") (pin "2") (pinfunction "2_2") (pintype "passive"))
    )
    (net (code "75") (name "unconnected-(CON10-Pad1)") (class "Default")
      (node (ref "CON10") (pin "1") (pinfunction "1_1") (pintype "passive"))
    )
    (net (code "76") (name "unconnected-(CON11-Pad1)") (class "Default")
      (node (ref "CON11") (pin "1") (pinfunction "1_1") (pintype "passive"))
    )
    (net (code "77") (name "unconnected-(CON12-Pad1)") (class "Default")
      (node (ref "CON12") (pin "1") (pinfunction "1_1") (pintype "passive"))
    )
    (net (code "78") (name "unconnected-(CON13-Pad1)") (class "Default")
      (node (ref "CON13") (pin "1") (pinfunction "1_1") (pintype "passive"))
    )
    (net (code "79") (name "unconnected-(CON14-Pad1)") (class "Default")
      (node (ref "CON14") (pin "1") (pinfunction "1_1") (pintype "passive"))
    )
    (net (code "80") (name "unconnected-(CON15-Pad1)") (class "Default")
      (node (ref "CON15") (pin "1") (pinfunction "1_1") (pintype "passive"))
    )
    (net (code "81") (name "unconnected-(IC1-D1-Pad5)") (class "Default")
      (node (ref "IC1") (pin "5") (pinfunction "D1_5") (pintype "bidirectional"))
    )
    (net (code "82") (name "unconnected-(IC1-D2-Pad6)") (class "Default")
      (node (ref "IC1") (pin "6") (pinfunction "D2_6") (pintype "bidirectional"))
    )
    (net (code "83") (name "unconnected-(IC2-D1-Pad5)") (class "Default")
      (node (ref "IC2") (pin "5") (pinfunction "D1_5") (pintype "bidirectional"))
    )
    (net (code "84") (name "unconnected-(IC2-D2-Pad6)") (class "Default")
      (node (ref "IC2") (pin "6") (pinfunction "D2_6") (pintype "bidirectional"))
    )
    (net (code "85") (name "unconnected-(J1-ID-Pad4)") (class "Default")
      (node (ref "J1") (pin "4") (pinfunction "ID_4") (pintype "passive"))
    )
    (net (code "86") (name "unconnected-(MODULE2-NC-Pad35)") (class "Default")
      (node (ref "MODULE2") (pin "35") (pinfunction "NC_35") (pintype "no_connect"))
    )
    (net (code "87") (name "unconnected-(MODULE2-POWER_ENABLE_IN-Pad18)") (class "Default")
      (node (ref "MODULE2") (pin "18") (pinfunction "POWER_ENABLE_IN_18") (pintype "input"))
    )
  )
)
